# SCH__Atlas_2026-06-22.net
KiCad netlist of a schematic drawn in EasyEDA
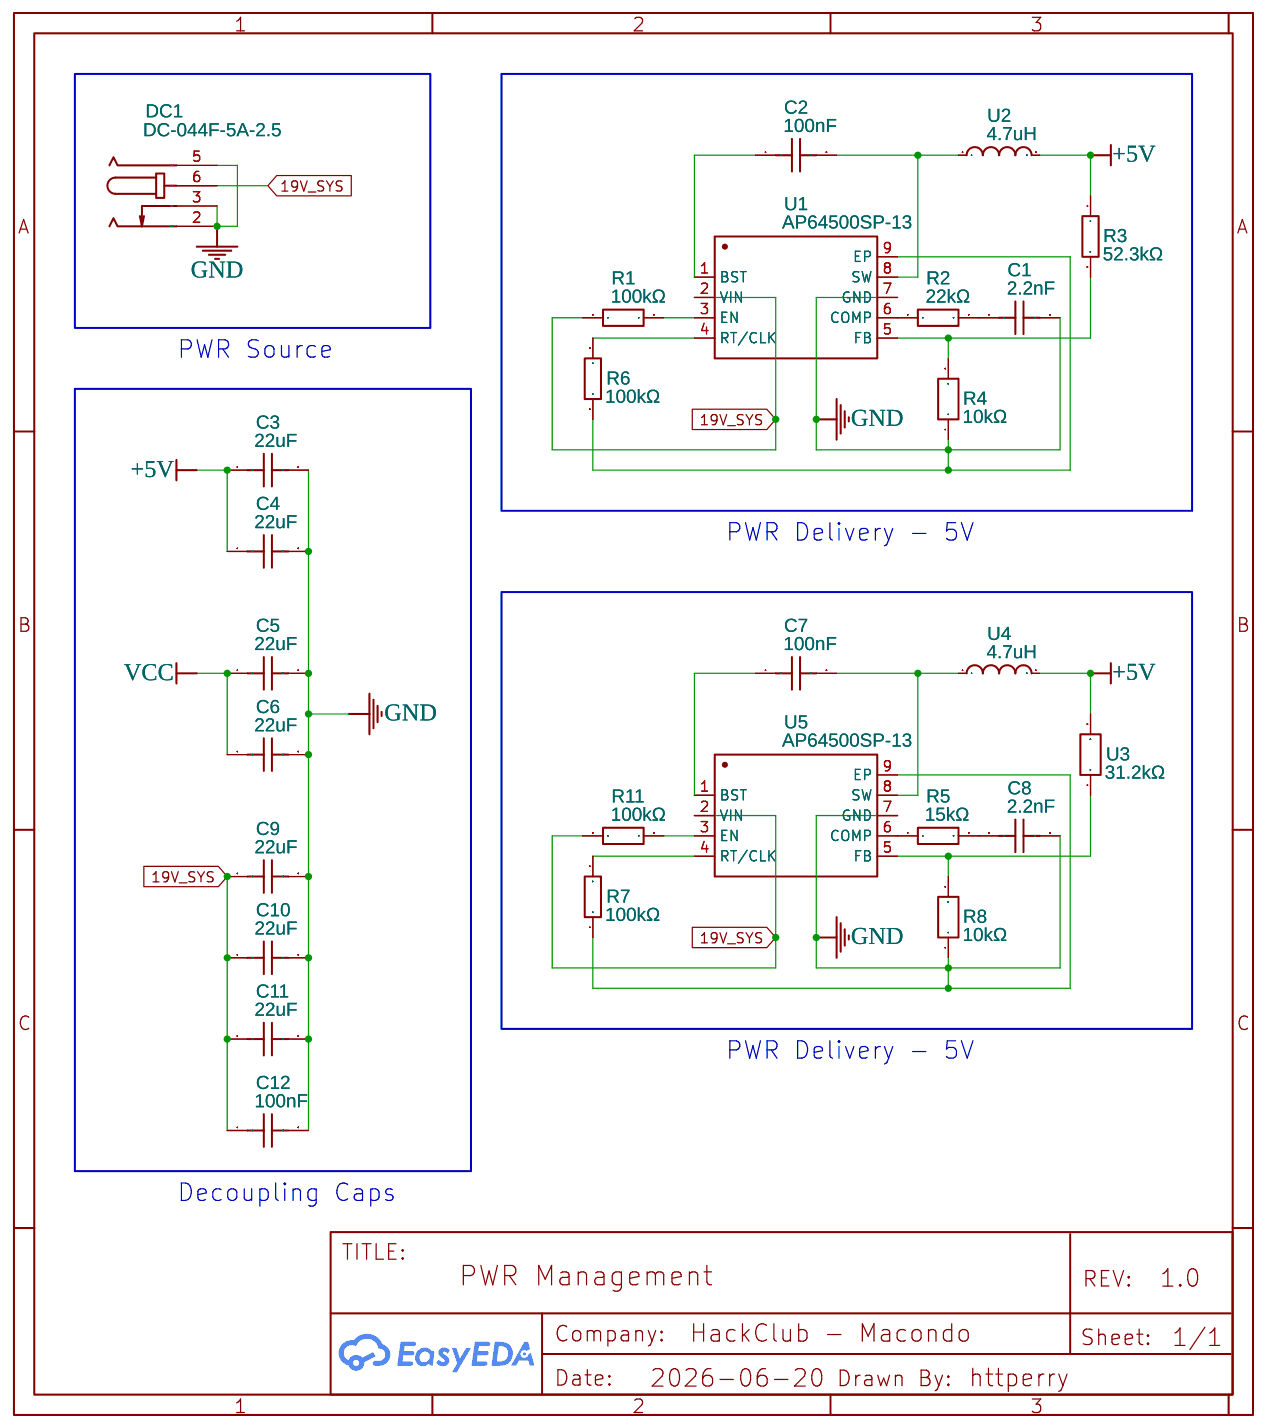
[diagram p0: PWR_Management]
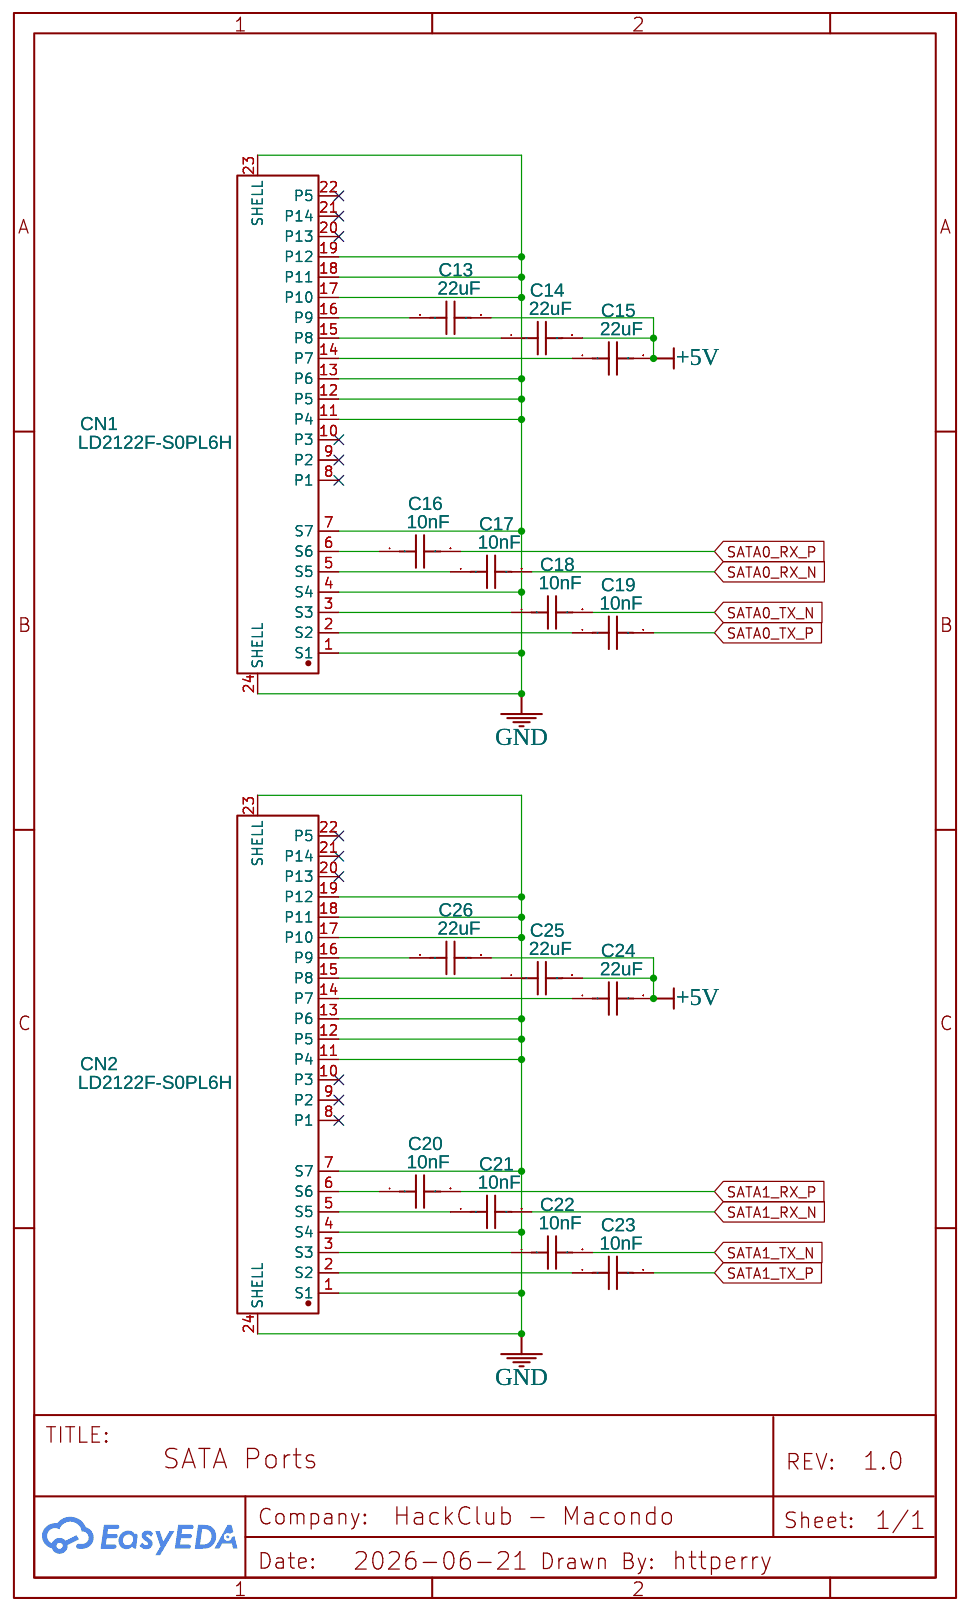
[diagram p1: SATA_Ports]
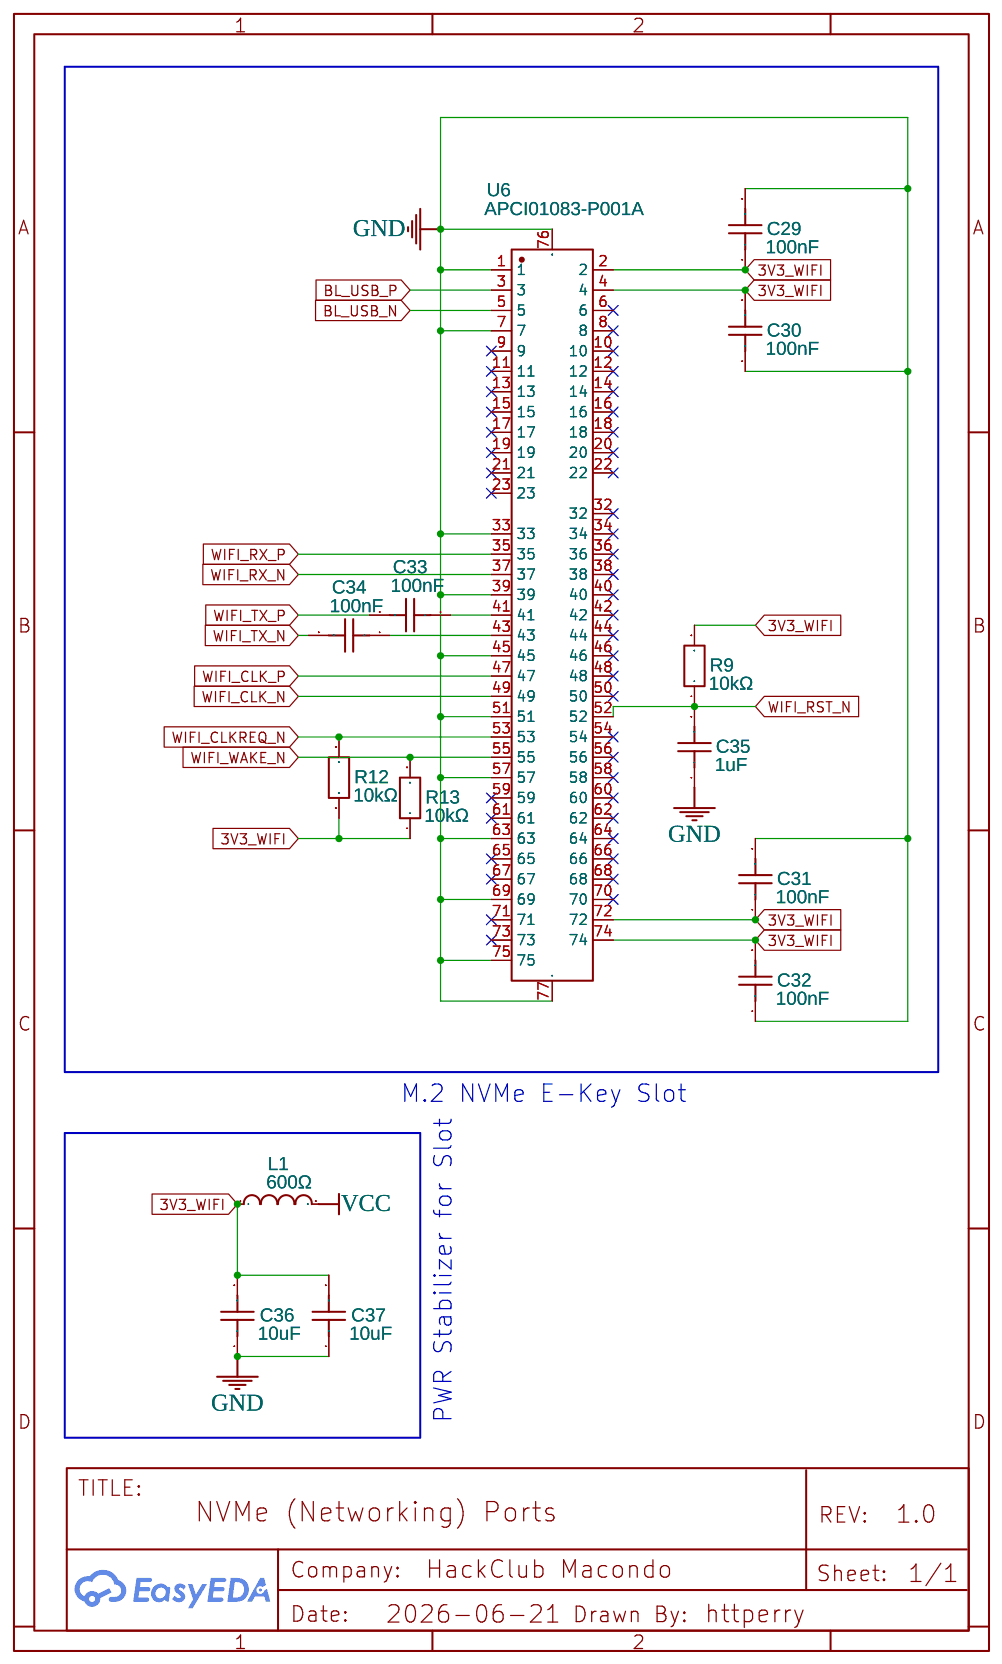
[diagram p2: NVMe_(Networking)_Ports]
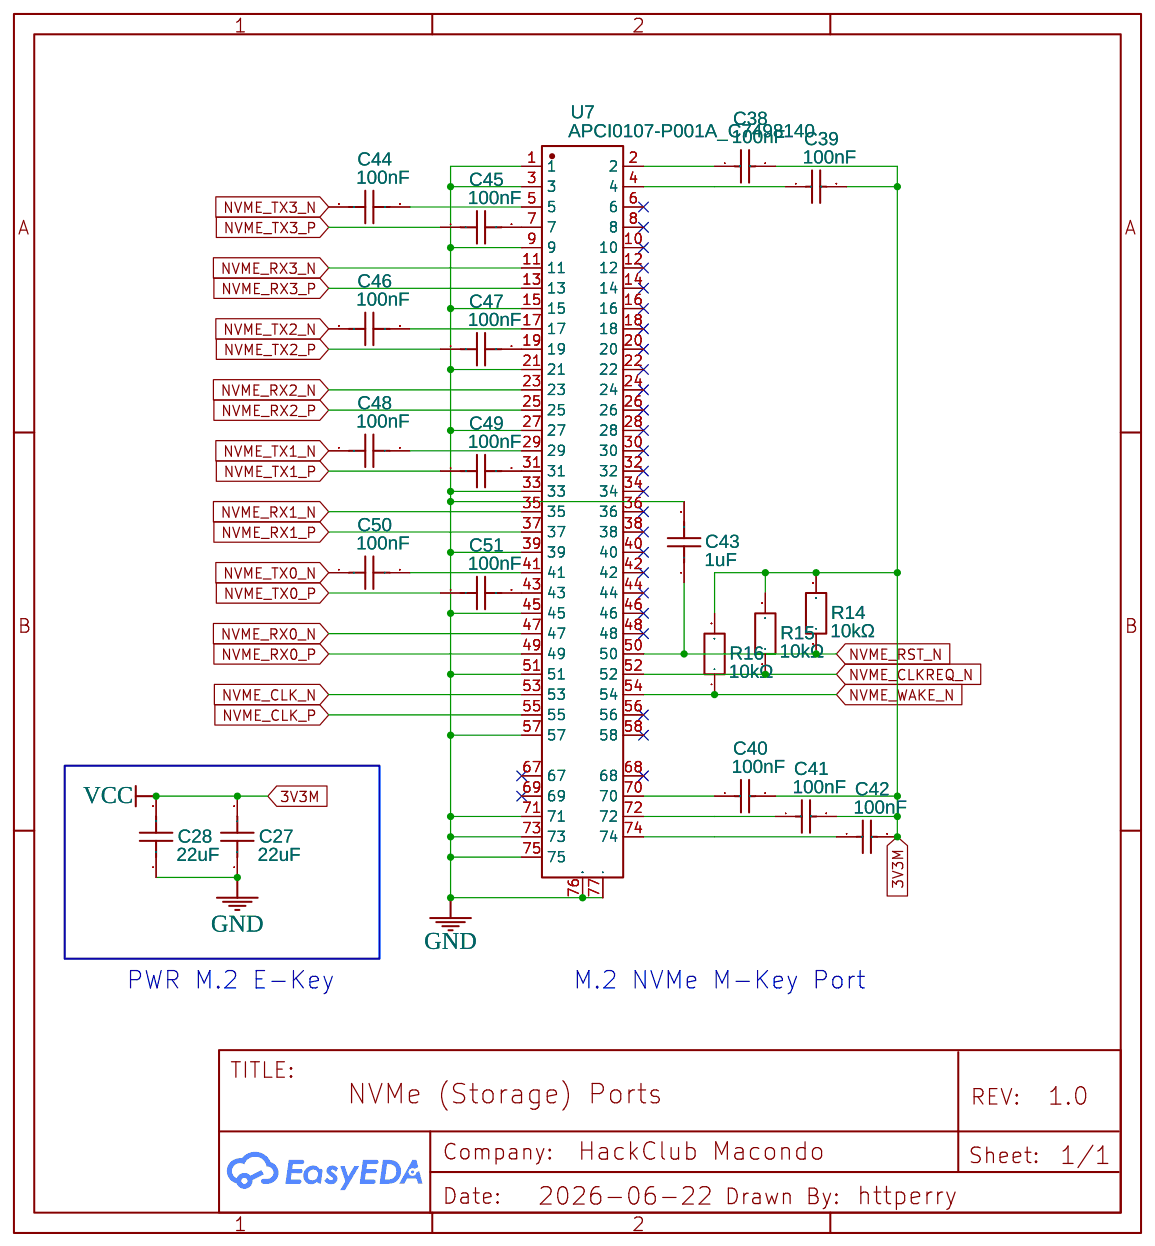
[diagram p3: NVMe_(Storage)_Ports]
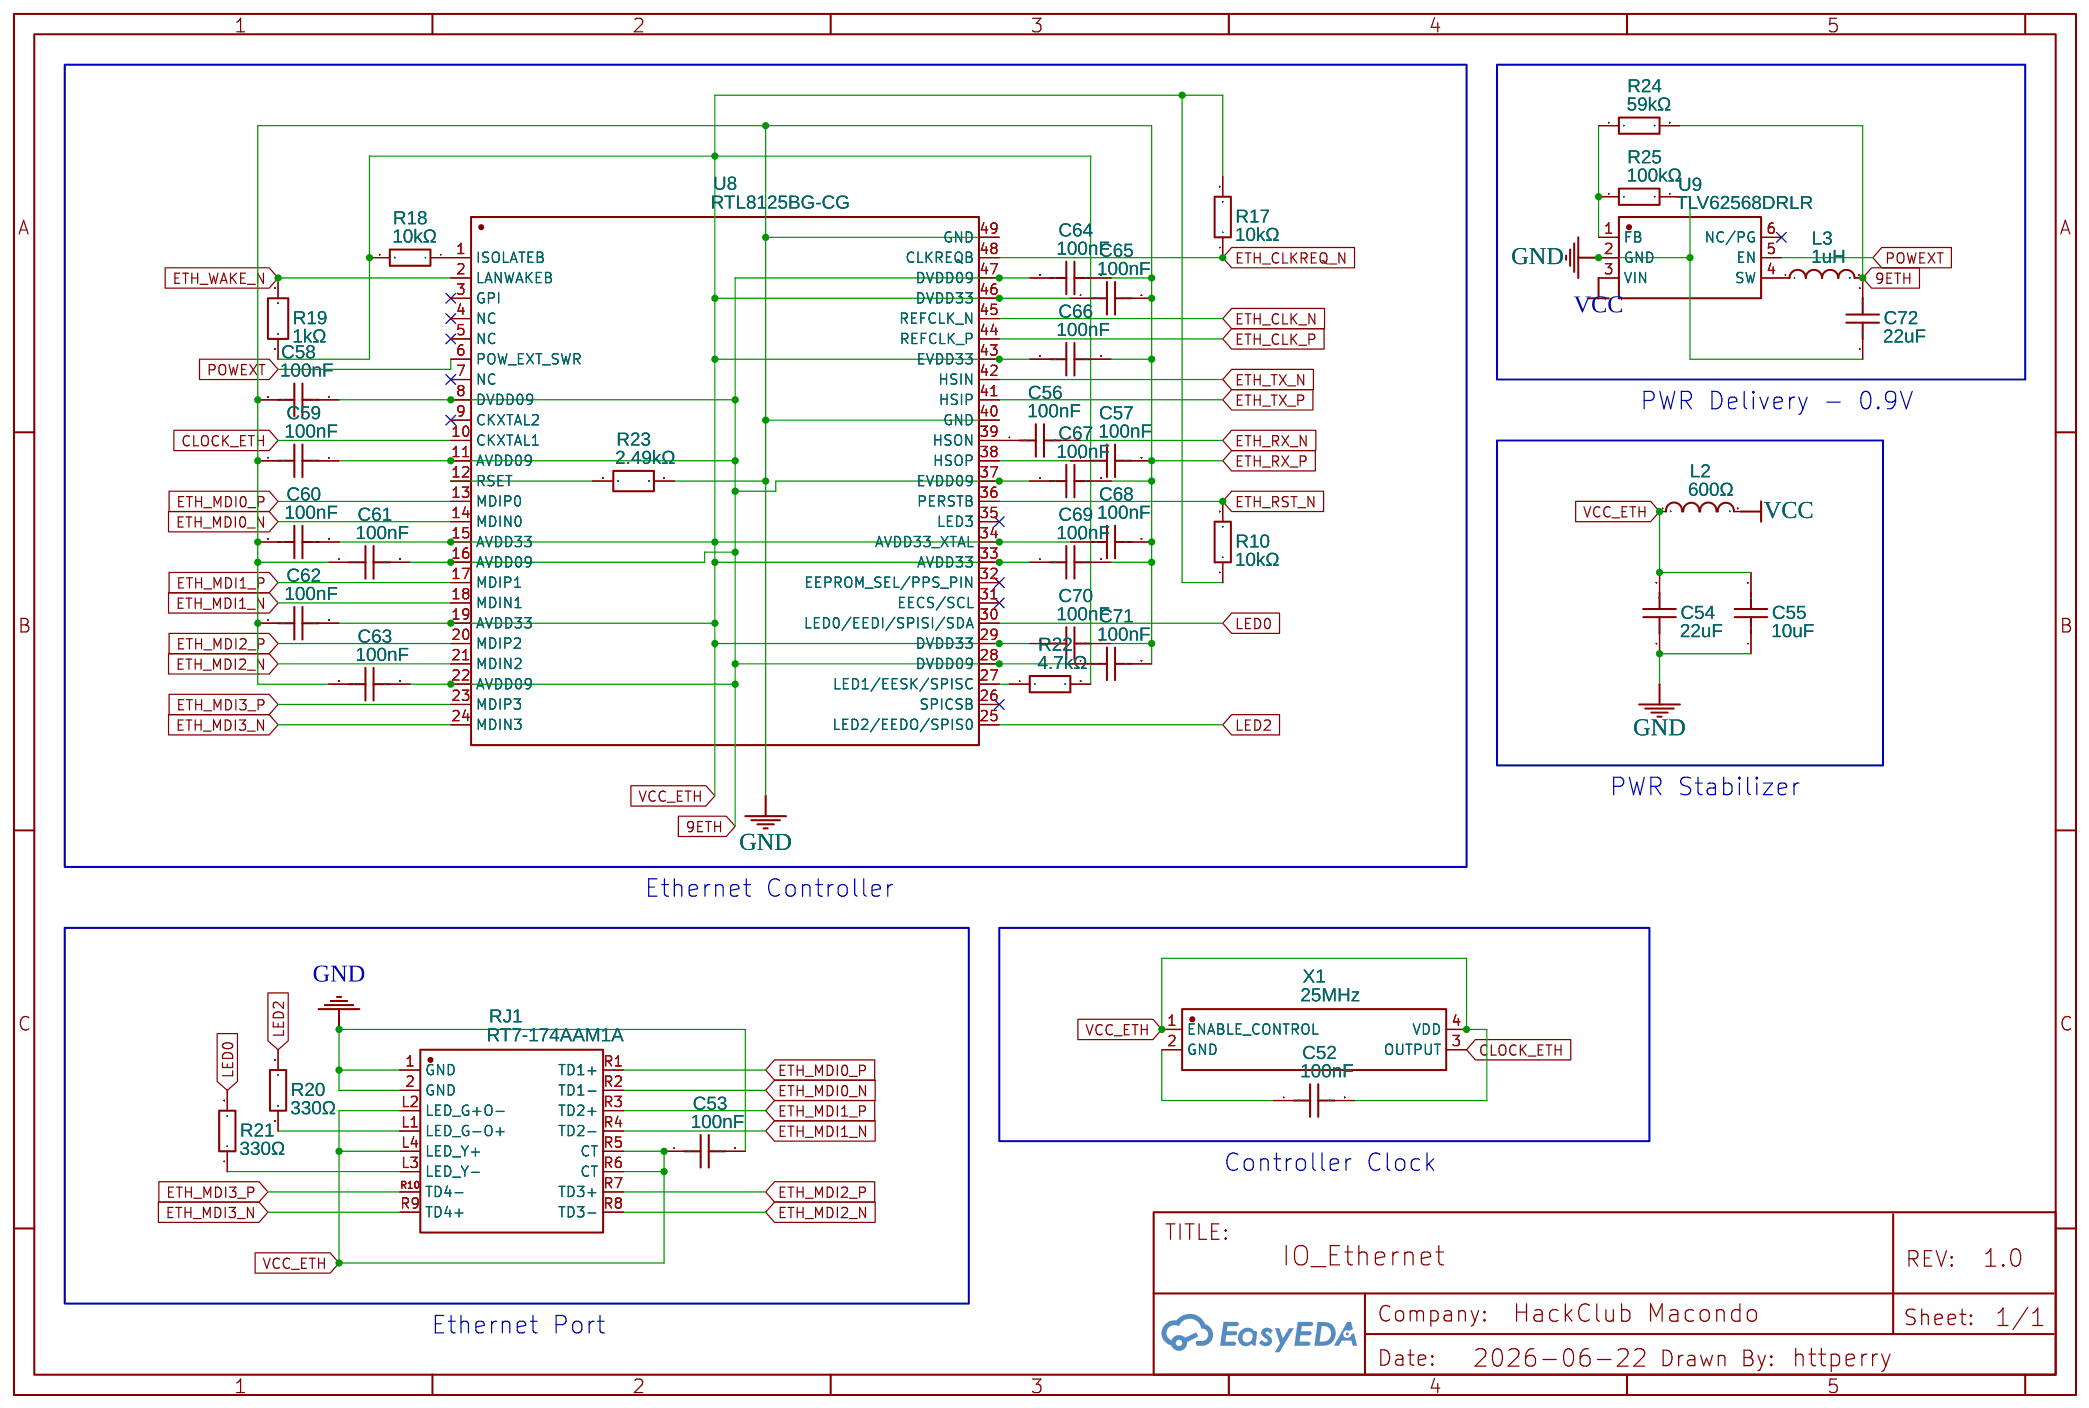
[diagram p4: IO_Ethernet]

(export (version "E")
  (design (tool "Eeschema 10.0.6"))
  (components
    (comp (ref "C1")
      (value "2.2nF")
      (fields
        (field (name "Manufacturer Part") "FCC0603B222K500CT")
        (field (name "Manufacturer") "FOJAN(富捷)")
      )
      (libsource (lib "") (part "FCC0603B222K500CT"))
    )
    (comp (ref "C2")
      (value "100nF")
      (fields
        (field (name "Manufacturer Part") "GRM188R71H104KA93D")
        (field (name "Manufacturer") "muRata(村田)")
      )
      (libsource (lib "") (part "GRM188R71H104KA93D"))
    )
    (comp (ref "C3")
      (value "22uF")
      (fields
        (field (name "Manufacturer Part") "HGC0603R5226M160NTHJ")
        (field (name "Manufacturer") "Chinocera(华瓷)")
      )
      (libsource (lib "") (part "HGC0603R5226M160NTHJ"))
    )
    (comp (ref "C4")
      (value "22uF")
      (fields
        (field (name "Manufacturer Part") "HGC0603R5226M160NTHJ")
        (field (name "Manufacturer") "Chinocera(华瓷)")
      )
      (libsource (lib "") (part "HGC0603R5226M160NTHJ"))
    )
    (comp (ref "C5")
      (value "22uF")
      (fields
        (field (name "Manufacturer Part") "HGC0603R5226M160NTHJ")
        (field (name "Manufacturer") "Chinocera(华瓷)")
      )
      (libsource (lib "") (part "HGC0603R5226M160NTHJ"))
    )
    (comp (ref "C6")
      (value "22uF")
      (fields
        (field (name "Manufacturer Part") "HGC0603R5226M160NTHJ")
        (field (name "Manufacturer") "Chinocera(华瓷)")
      )
      (libsource (lib "") (part "HGC0603R5226M160NTHJ"))
    )
    (comp (ref "C7")
      (value "100nF")
      (fields
        (field (name "Manufacturer Part") "GRM188R71H104KA93D")
        (field (name "Manufacturer") "muRata(村田)")
      )
      (libsource (lib "") (part "GRM188R71H104KA93D"))
    )
    (comp (ref "C8")
      (value "2.2nF")
      (fields
        (field (name "Manufacturer Part") "FCC0603B222K500CT")
        (field (name "Manufacturer") "FOJAN(富捷)")
      )
      (libsource (lib "") (part "FCC0603B222K500CT"))
    )
    (comp (ref "C9")
      (value "22uF")
      (fields
        (field (name "Manufacturer Part") "KCM55QR71H226KH13K")
        (field (name "Manufacturer") "muRata(村田)")
      )
      (libsource (lib "") (part "KCM55QR71H226KH13K"))
    )
    (comp (ref "C10")
      (value "22uF")
      (fields
        (field (name "Manufacturer Part") "KCM55QR71H226KH13K")
        (field (name "Manufacturer") "muRata(村田)")
      )
      (libsource (lib "") (part "KCM55QR71H226KH13K"))
    )
    (comp (ref "C11")
      (value "22uF")
      (fields
        (field (name "Manufacturer Part") "KCM55QR71H226KH13K")
        (field (name "Manufacturer") "muRata(村田)")
      )
      (libsource (lib "") (part "KCM55QR71H226KH13K"))
    )
    (comp (ref "C12")
      (value "100nF")
      (fields
        (field (name "Manufacturer Part") "GRM188R71H104KA93D")
        (field (name "Manufacturer") "muRata(村田)")
      )
      (libsource (lib "") (part "GRM188R71H104KA93D"))
    )
    (comp (ref "DC1")
      (value "DC-044F-5A-2.5")
      (fields (field (name "Manufacturer") "XKB Connection(中国星坤)"))
      (libsource (lib "") (part "DC-044F-5A-2.5"))
    )
    (comp (ref "R1")
      (value "100kΩ")
      (fields (field (name "Manufacturer Part") "RS-03K1003FT") (field (name "Manufacturer") "FH(风华)"))
      (libsource (lib "") (part "RS-03K1003FT_C115320_1"))
    )
    (comp (ref "R2")
      (value "22kΩ")
      (fields (field (name "Manufacturer Part") "RS-03K2202FT") (field (name "Manufacturer") "FH(风华)"))
      (libsource (lib "") (part "RS-03K2202FT"))
    )
    (comp (ref "R3")
      (value "52.3kΩ")
      (fields (field (name "Manufacturer Part") "RS-03K5232FT") (field (name "Manufacturer") "FH(风华)"))
      (libsource (lib "") (part "RS-03K5232FT"))
    )
    (comp (ref "R4")
      (value "10kΩ")
      (fields (field (name "Manufacturer Part") "AR03BTS1002") (field (name "Manufacturer") "Viking(光颉)"))
      (libsource (lib "") (part "AR03BTS1002"))
    )
    (comp (ref "R5")
      (value "15kΩ")
      (fields (field (name "Manufacturer Part") "CR0603FA1502G") (field (name "Manufacturer") "LIZ(丽智电子)"))
      (libsource (lib "") (part "CR0603FA1502G"))
    )
    (comp (ref "R6")
      (value "100kΩ")
      (fields (field (name "Manufacturer Part") "RS-03K1003FT") (field (name "Manufacturer") "FH(风华)"))
      (libsource (lib "") (part "RS-03K1003FT_C115320"))
    )
    (comp (ref "R7")
      (value "100kΩ")
      (fields (field (name "Manufacturer Part") "RS-03K1003FT") (field (name "Manufacturer") "FH(风华)"))
      (libsource (lib "") (part "RS-03K1003FT_C115320"))
    )
    (comp (ref "R8")
      (value "10kΩ")
      (fields (field (name "Manufacturer Part") "AR03BTS1002") (field (name "Manufacturer") "Viking(光颉)"))
      (libsource (lib "") (part "AR03BTS1002"))
    )
    (comp (ref "R11")
      (value "100kΩ")
      (fields (field (name "Manufacturer Part") "RS-03K1003FT") (field (name "Manufacturer") "FH(风华)"))
      (libsource (lib "") (part "RS-03K1003FT_C115320_1"))
    )
    (comp (ref "U1")
      (value "AP64500SP-13")
      (fields (field (name "Manufacturer") "DIODES(美台)"))
      (libsource (lib "") (part "AP64500SP-13"))
    )
    (comp (ref "U2")
      (value "4.7uH")
      (fields (field (name "Manufacturer Part") "APH0630T4R7M") (field (name "Manufacturer") "APV(爱普微)"))
      (libsource (lib "") (part "APH0630T4R7M"))
    )
    (comp (ref "U3")
      (value "31.2kΩ")
      (fields (field (name "Manufacturer Part") "RT0603DRE0731K2L") (field (name "Manufacturer") "YAGEO(国巨)"))
      (libsource (lib "") (part "RT0603DRE0731K2L"))
    )
    (comp (ref "U4")
      (value "4.7uH")
      (fields (field (name "Manufacturer Part") "APH0630T4R7M") (field (name "Manufacturer") "APV(爱普微)"))
      (libsource (lib "") (part "APH0630T4R7M"))
    )
    (comp (ref "U5")
      (value "AP64500SP-13")
      (fields (field (name "Manufacturer") "DIODES(美台)"))
      (libsource (lib "") (part "AP64500SP-13"))
    )
    (comp (ref "C13")
      (value "22uF")
      (fields
        (field (name "Manufacturer Part") "HGC0603R5226M160NTHJ")
        (field (name "Manufacturer") "Chinocera(华瓷)")
      )
      (libsource (lib "") (part "HGC0603R5226M160NTHJ"))
    )
    (comp (ref "C14")
      (value "22uF")
      (fields
        (field (name "Manufacturer Part") "HGC0603R5226M160NTHJ")
        (field (name "Manufacturer") "Chinocera(华瓷)")
      )
      (libsource (lib "") (part "HGC0603R5226M160NTHJ"))
    )
    (comp (ref "C15")
      (value "22uF")
      (fields
        (field (name "Manufacturer Part") "HGC0603R5226M160NTHJ")
        (field (name "Manufacturer") "Chinocera(华瓷)")
      )
      (libsource (lib "") (part "HGC0603R5226M160NTHJ"))
    )
    (comp (ref "C16")
      (value "10nF")
      (fields
        (field (name "Manufacturer Part") "FCC0402B103K500AT")
        (field (name "Manufacturer") "FOJAN(富捷)")
      )
      (libsource (lib "") (part "FCC0402B103K500AT"))
    )
    (comp (ref "C17")
      (value "10nF")
      (fields
        (field (name "Manufacturer Part") "FCC0402B103K500AT")
        (field (name "Manufacturer") "FOJAN(富捷)")
      )
      (libsource (lib "") (part "FCC0402B103K500AT"))
    )
    (comp (ref "C18")
      (value "10nF")
      (fields
        (field (name "Manufacturer Part") "FCC0402B103K500AT")
        (field (name "Manufacturer") "FOJAN(富捷)")
      )
      (libsource (lib "") (part "FCC0402B103K500AT"))
    )
    (comp (ref "C19")
      (value "10nF")
      (fields
        (field (name "Manufacturer Part") "FCC0402B103K500AT")
        (field (name "Manufacturer") "FOJAN(富捷)")
      )
      (libsource (lib "") (part "FCC0402B103K500AT"))
    )
    (comp (ref "C20")
      (value "10nF")
      (fields
        (field (name "Manufacturer Part") "FCC0402B103K500AT")
        (field (name "Manufacturer") "FOJAN(富捷)")
      )
      (libsource (lib "") (part "FCC0402B103K500AT"))
    )
    (comp (ref "C21")
      (value "10nF")
      (fields
        (field (name "Manufacturer Part") "FCC0402B103K500AT")
        (field (name "Manufacturer") "FOJAN(富捷)")
      )
      (libsource (lib "") (part "FCC0402B103K500AT"))
    )
    (comp (ref "C22")
      (value "10nF")
      (fields
        (field (name "Manufacturer Part") "FCC0402B103K500AT")
        (field (name "Manufacturer") "FOJAN(富捷)")
      )
      (libsource (lib "") (part "FCC0402B103K500AT"))
    )
    (comp (ref "C23")
      (value "10nF")
      (fields
        (field (name "Manufacturer Part") "FCC0402B103K500AT")
        (field (name "Manufacturer") "FOJAN(富捷)")
      )
      (libsource (lib "") (part "FCC0402B103K500AT"))
    )
    (comp (ref "C24")
      (value "22uF")
      (fields
        (field (name "Manufacturer Part") "HGC0603R5226M160NTHJ")
        (field (name "Manufacturer") "Chinocera(华瓷)")
      )
      (libsource (lib "") (part "HGC0603R5226M160NTHJ"))
    )
    (comp (ref "C25")
      (value "22uF")
      (fields
        (field (name "Manufacturer Part") "HGC0603R5226M160NTHJ")
        (field (name "Manufacturer") "Chinocera(华瓷)")
      )
      (libsource (lib "") (part "HGC0603R5226M160NTHJ"))
    )
    (comp (ref "C26")
      (value "22uF")
      (fields
        (field (name "Manufacturer Part") "HGC0603R5226M160NTHJ")
        (field (name "Manufacturer") "Chinocera(华瓷)")
      )
      (libsource (lib "") (part "HGC0603R5226M160NTHJ"))
    )
    (comp (ref "CN1")
      (value "LD2122F-S0PL6H")
      (fields (field (name "Manufacturer") "FOXCONN(富士康)"))
      (libsource (lib "") (part "LD2122F-S0PL6H"))
    )
    (comp (ref "CN2")
      (value "LD2122F-S0PL6H")
      (fields (field (name "Manufacturer") "FOXCONN(富士康)"))
      (libsource (lib "") (part "LD2122F-S0PL6H"))
    )
    (comp (ref "C29")
      (value "100nF")
      (fields
        (field (name "Manufacturer Part") "CC0402KRX5R6BB104")
        (field (name "Manufacturer") "YAGEO(国巨)")
      )
      (libsource (lib "") (part "CC0402KRX5R6BB104"))
    )
    (comp (ref "C30")
      (value "100nF")
      (fields
        (field (name "Manufacturer Part") "CC0402KRX5R6BB104")
        (field (name "Manufacturer") "YAGEO(国巨)")
      )
      (libsource (lib "") (part "CC0402KRX5R6BB104"))
    )
    (comp (ref "C31")
      (value "100nF")
      (fields
        (field (name "Manufacturer Part") "CC0402KRX5R6BB104")
        (field (name "Manufacturer") "YAGEO(国巨)")
      )
      (libsource (lib "") (part "CC0402KRX5R6BB104"))
    )
    (comp (ref "C32")
      (value "100nF")
      (fields
        (field (name "Manufacturer Part") "CC0402KRX5R6BB104")
        (field (name "Manufacturer") "YAGEO(国巨)")
      )
      (libsource (lib "") (part "CC0402KRX5R6BB104"))
    )
    (comp (ref "C33")
      (value "100nF")
      (fields
        (field (name "Manufacturer Part") "CC0402KRX5R6BB104")
        (field (name "Manufacturer") "YAGEO(国巨)")
      )
      (libsource (lib "") (part "CC0402KRX5R6BB104_1"))
    )
    (comp (ref "C34")
      (value "100nF")
      (fields
        (field (name "Manufacturer Part") "CC0402KRX5R6BB104")
        (field (name "Manufacturer") "YAGEO(国巨)")
      )
      (libsource (lib "") (part "CC0402KRX5R6BB104_1"))
    )
    (comp (ref "C35")
      (value "1uF")
      (fields
        (field (name "Manufacturer Part") "TCC0402X5R105K160AT")
        (field (name "Manufacturer") "CCTC(三环)")
      )
      (libsource (lib "") (part "TCC0402X5R105K160AT"))
    )
    (comp (ref "C36")
      (value "10uF")
      (fields
        (field (name "Manufacturer Part") "CGA0805X5R106K500MT")
        (field (name "Manufacturer") "HRE(芯声)")
      )
      (libsource (lib "") (part "CGA0805X5R106K500MT"))
    )
    (comp (ref "C37")
      (value "10uF")
      (fields
        (field (name "Manufacturer Part") "CGA0805X5R106K500MT")
        (field (name "Manufacturer") "HRE(芯声)")
      )
      (libsource (lib "") (part "CGA0805X5R106K500MT"))
    )
    (comp (ref "L1")
      (value "600Ω")
      (fields (field (name "Manufacturer Part") "MPZ2012S601AT000") (field (name "Manufacturer") "TDK"))
      (libsource (lib "") (part "MPZ2012S601AT000"))
    )
    (comp (ref "R9")
      (value "10kΩ")
      (fields (field (name "Manufacturer Part") "FRC0402F1002TS") (field (name "Manufacturer") "FOJAN(富捷)"))
      (libsource (lib "") (part "FRC0402F1002TS"))
    )
    (comp (ref "R12")
      (value "10kΩ")
      (fields (field (name "Manufacturer Part") "FRC0402F1002TS") (field (name "Manufacturer") "FOJAN(富捷)"))
      (libsource (lib "") (part "FRC0402F1002TS"))
    )
    (comp (ref "R13")
      (value "10kΩ")
      (fields (field (name "Manufacturer Part") "FRC0402F1002TS") (field (name "Manufacturer") "FOJAN(富捷)"))
      (libsource (lib "") (part "FRC0402F1002TS"))
    )
    (comp (ref "U6")
      (value "APCI01083-P001A")
      (fields (field (name "Manufacturer") "LX(连欣科技)"))
      (libsource (lib "") (part "APCI01083-P001A"))
    )
    (comp (ref "C27")
      (value "22uF")
      (fields
        (field (name "Manufacturer Part") "CL21A226MAYNNNE")
        (field (name "Manufacturer") "SAMSUNG(三星)")
      )
      (libsource (lib "") (part "CL21A226MAYNNNE"))
    )
    (comp (ref "C28")
      (value "22uF")
      (fields
        (field (name "Manufacturer Part") "CL21A226MAYNNNE")
        (field (name "Manufacturer") "SAMSUNG(三星)")
      )
      (libsource (lib "") (part "CL21A226MAYNNNE"))
    )
    (comp (ref "C38")
      (value "100nF")
      (fields
        (field (name "Manufacturer Part") "CC0402KRX5R8BB104")
        (field (name "Manufacturer") "YAGEO(国巨)")
      )
      (libsource (lib "") (part "CC0402KRX5R8BB104"))
    )
    (comp (ref "C39")
      (value "100nF")
      (fields
        (field (name "Manufacturer Part") "CC0402KRX5R8BB104")
        (field (name "Manufacturer") "YAGEO(国巨)")
      )
      (libsource (lib "") (part "CC0402KRX5R8BB104"))
    )
    (comp (ref "C40")
      (value "100nF")
      (fields
        (field (name "Manufacturer Part") "CC0402KRX5R8BB104")
        (field (name "Manufacturer") "YAGEO(国巨)")
      )
      (libsource (lib "") (part "CC0402KRX5R8BB104"))
    )
    (comp (ref "C41")
      (value "100nF")
      (fields
        (field (name "Manufacturer Part") "CC0402KRX5R8BB104")
        (field (name "Manufacturer") "YAGEO(国巨)")
      )
      (libsource (lib "") (part "CC0402KRX5R8BB104"))
    )
    (comp (ref "C42")
      (value "100nF")
      (fields
        (field (name "Manufacturer Part") "CC0402KRX5R8BB104")
        (field (name "Manufacturer") "YAGEO(国巨)")
      )
      (libsource (lib "") (part "CC0402KRX5R8BB104"))
    )
    (comp (ref "C43")
      (value "1uF")
      (fields
        (field (name "Manufacturer Part") "HGC0402R5105K500NTEJ")
        (field (name "Manufacturer") "Chinocera(华瓷)")
      )
      (libsource (lib "") (part "HGC0402R5105K500NTEJ"))
    )
    (comp (ref "C44")
      (value "100nF")
      (fields
        (field (name "Manufacturer Part") "GRM155R71H104KE14J")
        (field (name "Manufacturer") "muRata(村田)")
      )
      (libsource (lib "") (part "GRM155R71H104KE14J"))
    )
    (comp (ref "C45")
      (value "100nF")
      (fields
        (field (name "Manufacturer Part") "GRM155R71H104KE14J")
        (field (name "Manufacturer") "muRata(村田)")
      )
      (libsource (lib "") (part "GRM155R71H104KE14J"))
    )
    (comp (ref "C46")
      (value "100nF")
      (fields
        (field (name "Manufacturer Part") "GRM155R71H104KE14J")
        (field (name "Manufacturer") "muRata(村田)")
      )
      (libsource (lib "") (part "GRM155R71H104KE14J"))
    )
    (comp (ref "C47")
      (value "100nF")
      (fields
        (field (name "Manufacturer Part") "GRM155R71H104KE14J")
        (field (name "Manufacturer") "muRata(村田)")
      )
      (libsource (lib "") (part "GRM155R71H104KE14J"))
    )
    (comp (ref "C48")
      (value "100nF")
      (fields
        (field (name "Manufacturer Part") "GRM155R71H104KE14J")
        (field (name "Manufacturer") "muRata(村田)")
      )
      (libsource (lib "") (part "GRM155R71H104KE14J"))
    )
    (comp (ref "C49")
      (value "100nF")
      (fields
        (field (name "Manufacturer Part") "GRM155R71H104KE14J")
        (field (name "Manufacturer") "muRata(村田)")
      )
      (libsource (lib "") (part "GRM155R71H104KE14J"))
    )
    (comp (ref "C50")
      (value "100nF")
      (fields
        (field (name "Manufacturer Part") "GRM155R71H104KE14J")
        (field (name "Manufacturer") "muRata(村田)")
      )
      (libsource (lib "") (part "GRM155R71H104KE14J"))
    )
    (comp (ref "C51")
      (value "100nF")
      (fields
        (field (name "Manufacturer Part") "GRM155R71H104KE14J")
        (field (name "Manufacturer") "muRata(村田)")
      )
      (libsource (lib "") (part "GRM155R71H104KE14J"))
    )
    (comp (ref "R14")
      (value "10kΩ")
      (fields (field (name "Manufacturer Part") "FRC0402F1002TS") (field (name "Manufacturer") "FOJAN(富捷)"))
      (libsource (lib "") (part "FRC0402F1002TS"))
    )
    (comp (ref "R15")
      (value "10kΩ")
      (fields (field (name "Manufacturer Part") "FRC0402F1002TS") (field (name "Manufacturer") "FOJAN(富捷)"))
      (libsource (lib "") (part "FRC0402F1002TS"))
    )
    (comp (ref "R16")
      (value "10kΩ")
      (fields (field (name "Manufacturer Part") "FRC0402F1002TS") (field (name "Manufacturer") "FOJAN(富捷)"))
      (libsource (lib "") (part "FRC0402F1002TS"))
    )
    (comp (ref "U7")
      (value "APCI0107-P001A_C7498140")
      (fields (field (name "Manufacturer Part") "APCI0107-P001A") (field (name "Manufacturer") "LX(连欣科技)"))
      (libsource (lib "") (part "APCI0107-P001A_C7498140"))
    )
    (comp (ref "C52")
      (value "100nF")
      (fields
        (field (name "Manufacturer Part") "GRM155R71H104KE14J")
        (field (name "Manufacturer") "muRata(村田)")
      )
      (libsource (lib "") (part "GRM155R71H104KE14J"))
    )
    (comp (ref "C53")
      (value "100nF")
      (fields
        (field (name "Manufacturer Part") "GRM155R71H104KE14J")
        (field (name "Manufacturer") "muRata(村田)")
      )
      (libsource (lib "") (part "GRM155R71H104KE14J"))
    )
    (comp (ref "C54")
      (value "22uF")
      (fields
        (field (name "Manufacturer Part") "GRT21BR61E226ME13L")
        (field (name "Manufacturer") "muRata(村田)")
      )
      (libsource (lib "") (part "GRT21BR61E226ME13L"))
    )
    (comp (ref "C55")
      (value "10uF")
      (fields
        (field (name "Manufacturer Part") "TCC0805X5R106K250FT")
        (field (name "Manufacturer") "CCTC(三环)")
      )
      (libsource (lib "") (part "TCC0805X5R106K250FT"))
    )
    (comp (ref "C56")
      (value "100nF")
      (fields
        (field (name "Manufacturer Part") "GRM155R71H104KE14J")
        (field (name "Manufacturer") "muRata(村田)")
      )
      (libsource (lib "") (part "GRM155R71H104KE14J"))
    )
    (comp (ref "C57")
      (value "100nF")
      (fields
        (field (name "Manufacturer Part") "GRM155R71H104KE14J")
        (field (name "Manufacturer") "muRata(村田)")
      )
      (libsource (lib "") (part "GRM155R71H104KE14J"))
    )
    (comp (ref "C58")
      (value "100nF")
      (fields
        (field (name "Manufacturer Part") "GRM155R71H104KE14J")
        (field (name "Manufacturer") "muRata(村田)")
      )
      (libsource (lib "") (part "GRM155R71H104KE14J_1"))
    )
    (comp (ref "C59")
      (value "100nF")
      (fields
        (field (name "Manufacturer Part") "GRM155R71H104KE14J")
        (field (name "Manufacturer") "muRata(村田)")
      )
      (libsource (lib "") (part "GRM155R71H104KE14J"))
    )
    (comp (ref "C60")
      (value "100nF")
      (fields
        (field (name "Manufacturer Part") "GRM155R71H104KE14J")
        (field (name "Manufacturer") "muRata(村田)")
      )
      (libsource (lib "") (part "GRM155R71H104KE14J"))
    )
    (comp (ref "C61")
      (value "100nF")
      (fields
        (field (name "Manufacturer Part") "GRM155R71H104KE14J")
        (field (name "Manufacturer") "muRata(村田)")
      )
      (libsource (lib "") (part "GRM155R71H104KE14J"))
    )
    (comp (ref "C62")
      (value "100nF")
      (fields
        (field (name "Manufacturer Part") "GRM155R71H104KE14J")
        (field (name "Manufacturer") "muRata(村田)")
      )
      (libsource (lib "") (part "GRM155R71H104KE14J"))
    )
    (comp (ref "C63")
      (value "100nF")
      (fields
        (field (name "Manufacturer Part") "GRM155R71H104KE14J")
        (field (name "Manufacturer") "muRata(村田)")
      )
      (libsource (lib "") (part "GRM155R71H104KE14J"))
    )
    (comp (ref "C64")
      (value "100nF")
      (fields
        (field (name "Manufacturer Part") "GRM155R71H104KE14J")
        (field (name "Manufacturer") "muRata(村田)")
      )
      (libsource (lib "") (part "GRM155R71H104KE14J"))
    )
    (comp (ref "C65")
      (value "100nF")
      (fields
        (field (name "Manufacturer Part") "GRM155R71H104KE14J")
        (field (name "Manufacturer") "muRata(村田)")
      )
      (libsource (lib "") (part "GRM155R71H104KE14J"))
    )
    (comp (ref "C66")
      (value "100nF")
      (fields
        (field (name "Manufacturer Part") "GRM155R71H104KE14J")
        (field (name "Manufacturer") "muRata(村田)")
      )
      (libsource (lib "") (part "GRM155R71H104KE14J"))
    )
    (comp (ref "C67")
      (value "100nF")
      (fields
        (field (name "Manufacturer Part") "GRM155R71H104KE14J")
        (field (name "Manufacturer") "muRata(村田)")
      )
      (libsource (lib "") (part "GRM155R71H104KE14J"))
    )
    (comp (ref "C68")
      (value "100nF")
      (fields
        (field (name "Manufacturer Part") "GRM155R71H104KE14J")
        (field (name "Manufacturer") "muRata(村田)")
      )
      (libsource (lib "") (part "GRM155R71H104KE14J"))
    )
    (comp (ref "C69")
      (value "100nF")
      (fields
        (field (name "Manufacturer Part") "GRM155R71H104KE14J")
        (field (name "Manufacturer") "muRata(村田)")
      )
      (libsource (lib "") (part "GRM155R71H104KE14J"))
    )
    (comp (ref "C70")
      (value "100nF")
      (fields
        (field (name "Manufacturer Part") "GRM155R71H104KE14J")
        (field (name "Manufacturer") "muRata(村田)")
      )
      (libsource (lib "") (part "GRM155R71H104KE14J"))
    )
    (comp (ref "C71")
      (value "100nF")
      (fields
        (field (name "Manufacturer Part") "GRM155R71H104KE14J")
        (field (name "Manufacturer") "muRata(村田)")
      )
      (libsource (lib "") (part "GRM155R71H104KE14J"))
    )
    (comp (ref "C72")
      (value "22uF")
      (fields
        (field (name "Manufacturer Part") "GRT21BR61E226ME13L")
        (field (name "Manufacturer") "muRata(村田)")
      )
      (libsource (lib "") (part "GRT21BR61E226ME13L"))
    )
    (comp (ref "L2")
      (value "600Ω")
      (fields (field (name "Manufacturer Part") "MPZ2012S601AT000") (field (name "Manufacturer") "TDK"))
      (libsource (lib "") (part "MPZ2012S601AT000"))
    )
    (comp (ref "L3")
      (value "1uH")
      (fields (field (name "Manufacturer Part") "XRIM201612S1R0MBCA") (field (name "Manufacturer") "XR(祥如)"))
      (libsource (lib "") (part "XRIM201612S1R0MBCA"))
    )
    (comp (ref "R10")
      (value "10kΩ")
      (fields (field (name "Manufacturer Part") "ERA2AEB103X") (field (name "Manufacturer") "PANASONIC(松下)"))
      (libsource (lib "") (part "ERA2AEB103X"))
    )
    (comp (ref "R17")
      (value "10kΩ")
      (fields (field (name "Manufacturer Part") "ERA2AEB103X") (field (name "Manufacturer") "PANASONIC(松下)"))
      (libsource (lib "") (part "ERA2AEB103X"))
    )
    (comp (ref "R18")
      (value "10kΩ")
      (fields (field (name "Manufacturer Part") "ERA2AEB103X") (field (name "Manufacturer") "PANASONIC(松下)"))
      (libsource (lib "") (part "ERA2AEB103X_1"))
    )
    (comp (ref "R19")
      (value "1kΩ")
      (fields (field (name "Manufacturer Part") "RT0402BRD071KL") (field (name "Manufacturer") "YAGEO(国巨)"))
      (libsource (lib "") (part "RT0402BRD071KL"))
    )
    (comp (ref "R20")
      (value "330Ω")
      (fields (field (name "Manufacturer Part") "RC0402JR-07330RL") (field (name "Manufacturer") "YAGEO(国巨)"))
      (libsource (lib "") (part "RC0402JR-07330RL_1"))
    )
    (comp (ref "R21")
      (value "330Ω")
      (fields (field (name "Manufacturer Part") "RC0402JR-07330RL") (field (name "Manufacturer") "YAGEO(国巨)"))
      (libsource (lib "") (part "RC0402JR-07330RL"))
    )
    (comp (ref "R22")
      (value "4.7kΩ")
      (fields (field (name "Manufacturer Part") "RC0402FR-074K7L") (field (name "Manufacturer") "YAGEO(国巨)"))
      (libsource (lib "") (part "RC0402FR-074K7L"))
    )
    (comp (ref "R23")
      (value "2.49kΩ")
      (fields (field (name "Manufacturer Part") "FRC0402F2491TS") (field (name "Manufacturer") "FOJAN(富捷)"))
      (libsource (lib "") (part "FRC0402F2491TS"))
    )
    (comp (ref "R24")
      (value "59kΩ")
      (fields (field (name "Manufacturer Part") "RS-03K5902FT") (field (name "Manufacturer") "FH(风华)"))
      (libsource (lib "") (part "RS-03K5902FT"))
    )
    (comp (ref "R25")
      (value "100kΩ")
      (fields (field (name "Manufacturer Part") "RS-03K1003FT") (field (name "Manufacturer") "FH(风华)"))
      (libsource (lib "") (part "RS-03K1003FT_C115320"))
    )
    (comp (ref "RJ1")
      (value "RT7-174AAM1A")
      (fields (field (name "Manufacturer") "UDE(涌德电子)"))
      (libsource (lib "") (part "RT7-174AAM1A"))
    )
    (comp (ref "U8")
      (value "RTL8125BG-CG")
      (fields (field (name "Manufacturer") "REALTEK(瑞昱)"))
      (libsource (lib "") (part "RTL8125BG-CG"))
    )
    (comp (ref "U9")
      (value "TLV62568DRLR")
      (fields (field (name "Manufacturer") "TI(德州仪器)"))
      (libsource (lib "") (part "TLV62568DRLR"))
    )
    (comp (ref "X1")
      (value "25MHz")
      (fields
        (field (name "Manufacturer Part") "SX3M25.000B10G40TNN")
        (field (name "Manufacturer") "SCTF(星通时频)")
      )
      (libsource (lib "") (part "SX3M25.000B10G40TNN"))
    )
  )
  (nets
    (net (code "1") (name "+5V") (class "Default")
      (node (ref "C13") (pin "2") (pinfunction "2_2") (pintype "unspecified"))
      (node (ref "C14") (pin "2") (pinfunction "2_2") (pintype "unspecified"))
      (node (ref "C15") (pin "2") (pinfunction "2_2") (pintype "unspecified"))
      (node (ref "C24") (pin "2") (pinfunction "2_2") (pintype "unspecified"))
      (node (ref "C25") (pin "2") (pinfunction "2_2") (pintype "unspecified"))
      (node (ref "C26") (pin "2") (pinfunction "2_2") (pintype "unspecified"))
      (node (ref "C3") (pin "1") (pinfunction "1_1") (pintype "unspecified"))
      (node (ref "C4") (pin "1") (pinfunction "1_1") (pintype "unspecified"))
      (node (ref "R3") (pin "1") (pinfunction "1_1") (pintype "unspecified"))
      (node (ref "U2") (pin "2") (pinfunction "2_2") (pintype "unspecified"))
      (node (ref "U3") (pin "2") (pinfunction "2_2") (pintype "unspecified"))
      (node (ref "U4") (pin "2") (pinfunction "2_2") (pintype "unspecified"))
    )
    (net (code "2") (name "3V3M") (class "Default")
      (node (ref "C27") (pin "2") (pinfunction "2_2") (pintype "unspecified"))
      (node (ref "C28") (pin "2") (pinfunction "2_2") (pintype "unspecified"))
      (node (ref "C38") (pin "2") (pinfunction "2_2") (pintype "input"))
      (node (ref "C39") (pin "2") (pinfunction "2_2") (pintype "input"))
      (node (ref "C40") (pin "2") (pinfunction "2_2") (pintype "input"))
      (node (ref "C41") (pin "2") (pinfunction "2_2") (pintype "input"))
      (node (ref "C42") (pin "2") (pinfunction "2_2") (pintype "input"))
      (node (ref "C5") (pin "1") (pinfunction "1_1") (pintype "unspecified"))
      (node (ref "C6") (pin "1") (pinfunction "1_1") (pintype "unspecified"))
      (node (ref "L1") (pin "2") (pinfunction "2_2") (pintype "unspecified"))
      (node (ref "L2") (pin "2") (pinfunction "2_2") (pintype "unspecified"))
      (node (ref "R14") (pin "2") (pinfunction "2_2") (pintype "unspecified"))
      (node (ref "R15") (pin "2") (pinfunction "2_2") (pintype "unspecified"))
      (node (ref "R16") (pin "2") (pinfunction "2_2") (pintype "unspecified"))
      (node (ref "U9") (pin "3") (pinfunction "VIN_3") (pintype "unspecified"))
    )
    (net (code "3") (name "3V3_WIFI") (class "Default")
      (node (ref "C29") (pin "1") (pinfunction "1_1") (pintype "unspecified"))
      (node (ref "C30") (pin "2") (pinfunction "2_2") (pintype "unspecified"))
      (node (ref "C31") (pin "1") (pinfunction "1_1") (pintype "unspecified"))
      (node (ref "C32") (pin "2") (pinfunction "2_2") (pintype "unspecified"))
      (node (ref "C36") (pin "2") (pinfunction "2_2") (pintype "unspecified"))
      (node (ref "C37") (pin "2") (pinfunction "2_2") (pintype "unspecified"))
      (node (ref "L1") (pin "1") (pinfunction "1_1") (pintype "unspecified"))
      (node (ref "R12") (pin "1") (pinfunction "1_1") (pintype "unspecified"))
      (node (ref "R13") (pin "1") (pinfunction "1_1") (pintype "unspecified"))
      (node (ref "R9") (pin "2") (pinfunction "2_2") (pintype "unspecified"))
      (node (ref "U6") (pin "2") (pinfunction "2_2") (pintype "unspecified"))
      (node (ref "U6") (pin "4") (pinfunction "4_4") (pintype "unspecified"))
      (node (ref "U6") (pin "72") (pinfunction "72_72") (pintype "unspecified"))
      (node (ref "U6") (pin "74") (pinfunction "74_74") (pintype "unspecified"))
    )
    (net (code "4") (name "9ETH") (class "Default")
      (node (ref "C58") (pin "1") (pinfunction "1_1") (pintype "unspecified"))
      (node (ref "C59") (pin "2") (pinfunction "2_2") (pintype "unspecified"))
      (node (ref "C61") (pin "2") (pinfunction "2_2") (pintype "unspecified"))
      (node (ref "C63") (pin "2") (pinfunction "2_2") (pintype "unspecified"))
      (node (ref "C64") (pin "1") (pinfunction "1_1") (pintype "unspecified"))
      (node (ref "C67") (pin "1") (pinfunction "1_1") (pintype "unspecified"))
      (node (ref "C71") (pin "1") (pinfunction "1_1") (pintype "unspecified"))
      (node (ref "C72") (pin "2") (pinfunction "2_2") (pintype "unspecified"))
      (node (ref "L3") (pin "2") (pinfunction "2_2") (pintype "unspecified"))
      (node (ref "R24") (pin "2") (pinfunction "2_2") (pintype "unspecified"))
      (node (ref "U8") (pin "11") (pinfunction "AVDD09_11") (pintype "unspecified"))
      (node (ref "U8") (pin "16") (pinfunction "AVDD09_16") (pintype "unspecified"))
      (node (ref "U8") (pin "22") (pinfunction "AVDD09_22") (pintype "unspecified"))
      (node (ref "U8") (pin "28") (pinfunction "DVDD09_28") (pintype "unspecified"))
      (node (ref "U8") (pin "37") (pinfunction "EVDD09_37") (pintype "unspecified"))
      (node (ref "U8") (pin "47") (pinfunction "DVDD09_47") (pintype "unspecified"))
      (node (ref "U8") (pin "8") (pinfunction "DVDD09_8") (pintype "unspecified"))
    )
    (net (code "5") (name "19V_SYS") (class "Default")
      (node (ref "C10") (pin "1") (pinfunction "1_1") (pintype "unspecified"))
      (node (ref "C11") (pin "1") (pinfunction "1_1") (pintype "unspecified"))
      (node (ref "C12") (pin "1") (pinfunction "1_1") (pintype "unspecified"))
      (node (ref "C9") (pin "1") (pinfunction "1_1") (pintype "unspecified"))
      (node (ref "DC1") (pin "6") (pinfunction "6_6") (pintype "unspecified"))
      (node (ref "R1") (pin "1") (pinfunction "1_1") (pintype "unspecified"))
      (node (ref "R11") (pin "1") (pinfunction "1_1") (pintype "unspecified"))
      (node (ref "U1") (pin "2") (pinfunction "VIN_2") (pintype "unspecified"))
      (node (ref "U5") (pin "2") (pinfunction "VIN_2") (pintype "unspecified"))
    )
    (net (code "6") (name "BL_USB_N") (class "Default")
      (node (ref "U6") (pin "5") (pinfunction "5_5") (pintype "unspecified"))
    )
    (net (code "7") (name "BL_USB_P") (class "Default")
      (node (ref "U6") (pin "3") (pinfunction "3_3") (pintype "unspecified"))
    )
    (net (code "8") (name "CLOCK_ETH") (class "Default")
      (node (ref "U8") (pin "10") (pinfunction "CKXTAL1_10") (pintype "unspecified"))
      (node (ref "X1") (pin "3") (pinfunction "OUTPUT_3") (pintype "unspecified"))
    )
    (net (code "9") (name "ETH_CLKREQ_N") (class "Default")
      (node (ref "R17") (pin "1") (pinfunction "1_1") (pintype "input"))
      (node (ref "U8") (pin "48") (pinfunction "CLKREQB_48") (pintype "unspecified"))
    )
    (net (code "10") (name "ETH_CLK_N") (class "Default")
      (node (ref "U8") (pin "45") (pinfunction "REFCLK_N_45") (pintype "unspecified"))
    )
    (net (code "11") (name "ETH_CLK_P") (class "Default")
      (node (ref "U8") (pin "44") (pinfunction "REFCLK_P_44") (pintype "unspecified"))
    )
    (net (code "12") (name "ETH_MDI0_N") (class "Default")
      (node (ref "RJ1") (pin "R2") (pinfunction "TD1-_R2") (pintype "unspecified"))
      (node (ref "U8") (pin "14") (pinfunction "MDIN0_14") (pintype "unspecified"))
    )
    (net (code "13") (name "ETH_MDI0_P") (class "Default")
      (node (ref "RJ1") (pin "R1") (pinfunction "TD1+_R1") (pintype "unspecified"))
      (node (ref "U8") (pin "13") (pinfunction "MDIP0_13") (pintype "unspecified"))
    )
    (net (code "14") (name "ETH_MDI1_N") (class "Default")
      (node (ref "RJ1") (pin "R4") (pinfunction "TD2-_R4") (pintype "unspecified"))
      (node (ref "U8") (pin "18") (pinfunction "MDIN1_18") (pintype "unspecified"))
    )
    (net (code "15") (name "ETH_MDI1_P") (class "Default")
      (node (ref "RJ1") (pin "R3") (pinfunction "TD2+_R3") (pintype "unspecified"))
      (node (ref "U8") (pin "17") (pinfunction "MDIP1_17") (pintype "unspecified"))
    )
    (net (code "16") (name "ETH_MDI2_N") (class "Default")
      (node (ref "RJ1") (pin "R8") (pinfunction "TD3-_R8") (pintype "unspecified"))
      (node (ref "U8") (pin "21") (pinfunction "MDIN2_21") (pintype "unspecified"))
    )
    (net (code "17") (name "ETH_MDI2_P") (class "Default")
      (node (ref "RJ1") (pin "R7") (pinfunction "TD3+_R7") (pintype "unspecified"))
      (node (ref "U8") (pin "20") (pinfunction "MDIP2_20") (pintype "unspecified"))
    )
    (net (code "18") (name "ETH_MDI3_N") (class "Default")
      (node (ref "RJ1") (pin "R9") (pinfunction "TD4+_R9") (pintype "unspecified"))
      (node (ref "U8") (pin "24") (pinfunction "MDIN3_24") (pintype "unspecified"))
    )
    (net (code "19") (name "ETH_MDI3_P") (class "Default")
      (node (ref "RJ1") (pin "R10") (pinfunction "TD4-_R10") (pintype "unspecified"))
      (node (ref "U8") (pin "23") (pinfunction "MDIP3_23") (pintype "unspecified"))
    )
    (net (code "20") (name "ETH_RST_N") (class "Default")
      (node (ref "R10") (pin "2") (pinfunction "2_2") (pintype "input"))
      (node (ref "U8") (pin "36") (pinfunction "PERSTB_36") (pintype "unspecified"))
    )
    (net (code "21") (name "ETH_RX_N") (class "Default")
      (node (ref "C56") (pin "2") (pinfunction "2_2") (pintype "unspecified"))
    )
    (net (code "22") (name "ETH_RX_P") (class "Default")
      (node (ref "C1") (pin "2") (pinfunction "2_2") (pintype "unspecified"))
      (node (ref "C10") (pin "2") (pinfunction "2_2") (pintype "unspecified"))
      (node (ref "C11") (pin "2") (pinfunction "2_2") (pintype "unspecified"))
      (node (ref "C12") (pin "2") (pinfunction "2_2") (pintype "unspecified"))
      (node (ref "C27") (pin "1") (pinfunction "1_1") (pintype "unspecified"))
      (node (ref "C28") (pin "1") (pinfunction "1_1") (pintype "unspecified"))
      (node (ref "C29") (pin "2") (pinfunction "2_2") (pintype "unspecified"))
      (node (ref "C3") (pin "2") (pinfunction "2_2") (pintype "unspecified"))
      (node (ref "C30") (pin "1") (pinfunction "1_1") (pintype "unspecified"))
      (node (ref "C31") (pin "2") (pinfunction "2_2") (pintype "unspecified"))
      (node (ref "C32") (pin "1") (pinfunction "1_1") (pintype "unspecified"))
      (node (ref "C35") (pin "1") (pinfunction "1_1") (pintype "unspecified"))
      (node (ref "C36") (pin "1") (pinfunction "1_1") (pintype "unspecified"))
      (node (ref "C37") (pin "1") (pinfunction "1_1") (pintype "unspecified"))
      (node (ref "C4") (pin "2") (pinfunction "2_2") (pintype "unspecified"))
      (node (ref "C43") (pin "2") (pinfunction "2_2") (pintype "unspecified"))
      (node (ref "C5") (pin "2") (pinfunction "2_2") (pintype "unspecified"))
      (node (ref "C53") (pin "2") (pinfunction "2_2") (pintype "unspecified"))
      (node (ref "C54") (pin "1") (pinfunction "1_1") (pintype "unspecified"))
      (node (ref "C55") (pin "1") (pinfunction "1_1") (pintype "unspecified"))
      (node (ref "C57") (pin "2") (pinfunction "2_2") (pintype "unspecified"))
      (node (ref "C58") (pin "2") (pinfunction "2_2") (pintype "unspecified"))
      (node (ref "C59") (pin "1") (pinfunction "1_1") (pintype "unspecified"))
      (node (ref "C6") (pin "2") (pinfunction "2_2") (pintype "unspecified"))
      (node (ref "C60") (pin "1") (pinfunction "1_1") (pintype "unspecified"))
      (node (ref "C61") (pin "1") (pinfunction "1_1") (pintype "unspecified"))
      (node (ref "C62") (pin "1") (pinfunction "1_1") (pintype "unspecified"))
      (node (ref "C63") (pin "1") (pinfunction "1_1") (pintype "unspecified"))
      (node (ref "C64") (pin "2") (pinfunction "2_2") (pintype "unspecified"))
      (node (ref "C65") (pin "2") (pinfunction "2_2") (pintype "unspecified"))
      (node (ref "C66") (pin "2") (pinfunction "2_2") (pintype "unspecified"))
      (node (ref "C67") (pin "2") (pinfunction "2_2") (pintype "unspecified"))
      (node (ref "C68") (pin "2") (pinfunction "2_2") (pintype "unspecified"))
      (node (ref "C69") (pin "2") (pinfunction "2_2") (pintype "unspecified"))
      (node (ref "C70") (pin "2") (pinfunction "2_2") (pintype "unspecified"))
      (node (ref "C71") (pin "2") (pinfunction "2_2") (pintype "unspecified"))
      (node (ref "C72") (pin "1") (pinfunction "1_1") (pintype "unspecified"))
      (node (ref "C8") (pin "2") (pinfunction "2_2") (pintype "unspecified"))
      (node (ref "C9") (pin "2") (pinfunction "2_2") (pintype "unspecified"))
      (node (ref "CN1") (pin "1") (pinfunction "S1_1") (pintype "unspecified"))
      (node (ref "CN1") (pin "11") (pinfunction "P4_11") (pintype "unspecified"))
      (node (ref "CN1") (pin "12") (pinfunction "P5_12") (pintype "unspecified"))
      (node (ref "CN1") (pin "13") (pinfunction "P6_13") (pintype "unspecified"))
      (node (ref "CN1") (pin "17") (pinfunction "P10_17") (pintype "unspecified"))
      (node (ref "CN1") (pin "18") (pinfunction "P11_18") (pintype "unspecified"))
      (node (ref "CN1") (pin "19") (pinfunction "P12_19") (pintype "unspecified"))
      (node (ref "CN1") (pin "23") (pinfunction "SHELL_23") (pintype "unspecified"))
      (node (ref "CN1") (pin "24") (pinfunction "SHELL_24") (pintype "unspecified"))
      (node (ref "CN1") (pin "4") (pinfunction "S4_4") (pintype "unspecified"))
      (node (ref "CN1") (pin "7") (pinfunction "S7_7") (pintype "unspecified"))
      (node (ref "CN2") (pin "1") (pinfunction "S1_1") (pintype "unspecified"))
      (node (ref "CN2") (pin "11") (pinfunction "P4_11") (pintype "unspecified"))
      (node (ref "CN2") (pin "12") (pinfunction "P5_12") (pintype "unspecified"))
      (node (ref "CN2") (pin "13") (pinfunction "P6_13") (pintype "unspecified"))
      (node (ref "CN2") (pin "17") (pinfunction "P10_17") (pintype "unspecified"))
      (node (ref "CN2") (pin "18") (pinfunction "P11_18") (pintype "unspecified"))
      (node (ref "CN2") (pin "19") (pinfunction "P12_19") (pintype "unspecified"))
      (node (ref "CN2") (pin "23") (pinfunction "SHELL_23") (pintype "unspecified"))
      (node (ref "CN2") (pin "24") (pinfunction "SHELL_24") (pintype "unspecified"))
      (node (ref "CN2") (pin "4") (pinfunction "S4_4") (pintype "unspecified"))
      (node (ref "CN2") (pin "7") (pinfunction "S7_7") (pintype "unspecified"))
      (node (ref "DC1") (pin "2") (pinfunction "2_2") (pintype "unspecified"))
      (node (ref "DC1") (pin "3") (pinfunction "3_3") (pintype "unspecified"))
      (node (ref "DC1") (pin "5") (pinfunction "5_5") (pintype "unspecified"))
      (node (ref "R23") (pin "1") (pinfunction "1_1") (pintype "unspecified"))
      (node (ref "R25") (pin "2") (pinfunction "2_2") (pintype "unspecified"))
      (node (ref "R4") (pin "1") (pinfunction "1_1") (pintype "unspecified"))
      (node (ref "R6") (pin "1") (pinfunction "1_1") (pintype "unspecified"))
      (node (ref "R7") (pin "1") (pinfunction "1_1") (pintype "unspecified"))
      (node (ref "R8") (pin "1") (pinfunction "1_1") (pintype "unspecified"))
      (node (ref "RJ1") (pin "1") (pinfunction "GND_1") (pintype "unspecified"))
      (node (ref "RJ1") (pin "2") (pinfunction "GND_2") (pintype "unspecified"))
      (node (ref "U1") (pin "7") (pinfunction "GND_7") (pintype "unspecified"))
      (node (ref "U1") (pin "9") (pinfunction "EP_9") (pintype "unspecified"))
      (node (ref "U5") (pin "7") (pinfunction "GND_7") (pintype "unspecified"))
      (node (ref "U5") (pin "9") (pinfunction "EP_9") (pintype "unspecified"))
      (node (ref "U6") (pin "1") (pinfunction "1_1") (pintype "unspecified"))
      (node (ref "U6") (pin "33") (pinfunction "33_33") (pintype "unspecified"))
      (node (ref "U6") (pin "39") (pinfunction "39_39") (pintype "unspecified"))
      (node (ref "U6") (pin "45") (pinfunction "45_45") (pintype "unspecified"))
      (node (ref "U6") (pin "51") (pinfunction "51_51") (pintype "unspecified"))
      (node (ref "U6") (pin "57") (pinfunction "57_57") (pintype "unspecified"))
      (node (ref "U6") (pin "63") (pinfunction "63_63") (pintype "unspecified"))
      (node (ref "U6") (pin "69") (pinfunction "69_69") (pintype "unspecified"))
      (node (ref "U6") (pin "7") (pinfunction "7_7") (pintype "unspecified"))
      (node (ref "U6") (pin "75") (pinfunction "75_75") (pintype "unspecified"))
      (node (ref "U6") (pin "76") (pinfunction "76_76") (pintype "unspecified"))
      (node (ref "U6") (pin "77") (pinfunction "77_77") (pintype "unspecified"))
      (node (ref "U7") (pin "1") (pinfunction "1_1") (pintype "unspecified"))
      (node (ref "U7") (pin "15") (pinfunction "15_15") (pintype "unspecified"))
      (node (ref "U7") (pin "21") (pinfunction "21_21") (pintype "unspecified"))
      (node (ref "U7") (pin "27") (pinfunction "27_27") (pintype "unspecified"))
      (node (ref "U7") (pin "3") (pinfunction "3_3") (pintype "unspecified"))
      (node (ref "U7") (pin "33") (pinfunction "33_33") (pintype "unspecified"))
      (node (ref "U7") (pin "39") (pinfunction "39_39") (pintype "unspecified"))
      (node (ref "U7") (pin "45") (pinfunction "45_45") (pintype "unspecified"))
      (node (ref "U7") (pin "51") (pinfunction "51_51") (pintype "unspecified"))
      (node (ref "U7") (pin "57") (pinfunction "57_57") (pintype "unspecified"))
      (node (ref "U7") (pin "71") (pinfunction "71_71") (pintype "unspecified"))
      (node (ref "U7") (pin "73") (pinfunction "73_73") (pintype "unspecified"))
      (node (ref "U7") (pin "75") (pinfunction "75_75") (pintype "unspecified"))
      (node (ref "U7") (pin "76") (pinfunction "76_76") (pintype "unspecified"))
      (node (ref "U7") (pin "77") (pinfunction "77_77") (pintype "unspecified"))
      (node (ref "U7") (pin "9") (pinfunction "9_9") (pintype "unspecified"))
      (node (ref "U8") (pin "40") (pinfunction "GND_40") (pintype "unspecified"))
      (node (ref "U8") (pin "49") (pinfunction "GND_49") (pintype "unspecified"))
      (node (ref "U9") (pin "2") (pinfunction "GND_2") (pintype "unspecified"))
    )
    (net (code "23") (name "ETH_TX_N") (class "Default")
      (node (ref "U8") (pin "42") (pinfunction "HSIN_42") (pintype "unspecified"))
    )
    (net (code "24") (name "ETH_TX_P") (class "Default")
      (node (ref "U8") (pin "41") (pinfunction "HSIP_41") (pintype "unspecified"))
    )
    (net (code "25") (name "ETH_WAKE_N") (class "Default")
      (node (ref "R19") (pin "2") (pinfunction "2_2") (pintype "unspecified"))
      (node (ref "U8") (pin "2") (pinfunction "LANWAKEB_2") (pintype "unspecified"))
    )
    (net (code "26") (name "LED0") (class "Default")
      (node (ref "R21") (pin "2") (pinfunction "2_2") (pintype "input"))
      (node (ref "U8") (pin "30") (pinfunction "LED0/EEDI/SPISI/SDA_30") (pintype "unspecified"))
    )
    (net (code "27") (name "LED2") (class "Default")
      (node (ref "R20") (pin "1") (pinfunction "1_1") (pintype "input"))
      (node (ref "U8") (pin "25") (pinfunction "LED2/EEDO/SPIS0_25") (pintype "unspecified"))
    )
    (net (code "28") (name "NVME_CLKREQ_N") (class "Default")
      (node (ref "R15") (pin "1") (pinfunction "1_1") (pintype "unspecified"))
      (node (ref "U7") (pin "52") (pinfunction "52_52") (pintype "unspecified"))
    )
    (net (code "29") (name "NVME_CLK_N") (class "Default")
      (node (ref "U7") (pin "53") (pinfunction "53_53") (pintype "unspecified"))
    )
    (net (code "30") (name "NVME_CLK_P") (class "Default")
      (node (ref "U7") (pin "55") (pinfunction "55_55") (pintype "unspecified"))
    )
    (net (code "31") (name "NVME_RST_N") (class "Default")
      (node (ref "C43") (pin "1") (pinfunction "1_1") (pintype "unspecified"))
      (node (ref "R14") (pin "1") (pinfunction "1_1") (pintype "unspecified"))
      (node (ref "U7") (pin "50") (pinfunction "50_50") (pintype "unspecified"))
    )
    (net (code "32") (name "NVME_RX0_N") (class "Default")
      (node (ref "U7") (pin "47") (pinfunction "47_47") (pintype "unspecified"))
    )
    (net (code "33") (name "NVME_RX0_P") (class "Default")
      (node (ref "U7") (pin "49") (pinfunction "49_49") (pintype "unspecified"))
    )
    (net (code "34") (name "NVME_RX1_N") (class "Default")
      (node (ref "U7") (pin "35") (pinfunction "35_35") (pintype "unspecified"))
    )
    (net (code "35") (name "NVME_RX1_P") (class "Default")
      (node (ref "U7") (pin "37") (pinfunction "37_37") (pintype "unspecified"))
    )
    (net (code "36") (name "NVME_RX2_N") (class "Default")
      (node (ref "U7") (pin "23") (pinfunction "23_23") (pintype "unspecified"))
    )
    (net (code "37") (name "NVME_RX2_P") (class "Default")
      (node (ref "U7") (pin "25") (pinfunction "25_25") (pintype "unspecified"))
    )
    (net (code "38") (name "NVME_RX3_N") (class "Default")
      (node (ref "U7") (pin "11") (pinfunction "11_11") (pintype "unspecified"))
    )
    (net (code "39") (name "NVME_RX3_P") (class "Default")
      (node (ref "U7") (pin "13") (pinfunction "13_13") (pintype "unspecified"))
    )
    (net (code "40") (name "NVME_TX0_N") (class "Default")
      (node (ref "C50") (pin "1") (pinfunction "1_1") (pintype "unspecified"))
    )
    (net (code "41") (name "NVME_TX0_P") (class "Default")
      (node (ref "C51") (pin "1") (pinfunction "1_1") (pintype "unspecified"))
    )
    (net (code "42") (name "NVME_TX1_N") (class "Default")
      (node (ref "C48") (pin "1") (pinfunction "1_1") (pintype "unspecified"))
    )
    (net (code "43") (name "NVME_TX1_P") (class "Default")
      (node (ref "C49") (pin "1") (pinfunction "1_1") (pintype "unspecified"))
    )
    (net (code "44") (name "NVME_TX2_N") (class "Default")
      (node (ref "C46") (pin "1") (pinfunction "1_1") (pintype "unspecified"))
    )
    (net (code "45") (name "NVME_TX2_P") (class "Default")
      (node (ref "C47") (pin "1") (pinfunction "1_1") (pintype "unspecified"))
    )
    (net (code "46") (name "NVME_TX3_N") (class "Default")
      (node (ref "C44") (pin "1") (pinfunction "1_1") (pintype "unspecified"))
    )
    (net (code "47") (name "NVME_TX3_P") (class "Default")
      (node (ref "C45") (pin "1") (pinfunction "1_1") (pintype "unspecified"))
    )
    (net (code "48") (name "NVME_WAKE_N") (class "Default")
      (node (ref "R16") (pin "1") (pinfunction "1_1") (pintype "unspecified"))
      (node (ref "U7") (pin "54") (pinfunction "54_54") (pintype "unspecified"))
    )
    (net (code "49") (name "Net-(C1-Pad1)") (class "Default")
      (node (ref "C1") (pin "1") (pinfunction "1_1") (pintype "unspecified"))
      (node (ref "R2") (pin "2") (pinfunction "2_2") (pintype "unspecified"))
    )
    (net (code "50") (name "Net-(C8-Pad1)") (class "Default")
      (node (ref "C8") (pin "1") (pinfunction "1_1") (pintype "unspecified"))
      (node (ref "R5") (pin "2") (pinfunction "2_2") (pintype "input"))
    )
    (net (code "51") (name "Net-(C33-Pad1)") (class "Default")
      (node (ref "C33") (pin "1") (pinfunction "1_1") (pintype "unspecified"))
      (node (ref "U6") (pin "41") (pinfunction "41_41") (pintype "unspecified"))
    )
    (net (code "52") (name "Net-(C34-Pad1)") (class "Default")
      (node (ref "C34") (pin "1") (pinfunction "1_1") (pintype "unspecified"))
      (node (ref "U6") (pin "43") (pinfunction "43_43") (pintype "unspecified"))
    )
    (net (code "53") (name "Net-(C38-Pad1)") (class "Default")
      (node (ref "C38") (pin "1") (pinfunction "1_1") (pintype "input"))
      (node (ref "U7") (pin "2") (pinfunction "2_2") (pintype "unspecified"))
    )
    (net (code "54") (name "Net-(C39-Pad1)") (class "Default")
      (node (ref "C39") (pin "1") (pinfunction "1_1") (pintype "input"))
      (node (ref "U7") (pin "4") (pinfunction "4_4") (pintype "unspecified"))
    )
    (net (code "55") (name "Net-(C40-Pad1)") (class "Default")
      (node (ref "C40") (pin "1") (pinfunction "1_1") (pintype "input"))
      (node (ref "U7") (pin "70") (pinfunction "70_70") (pintype "unspecified"))
    )
    (net (code "56") (name "Net-(C41-Pad1)") (class "Default")
      (node (ref "C41") (pin "1") (pinfunction "1_1") (pintype "input"))
      (node (ref "U7") (pin "72") (pinfunction "72_72") (pintype "unspecified"))
    )
    (net (code "57") (name "Net-(C42-Pad1)") (class "Default")
      (node (ref "C42") (pin "1") (pinfunction "1_1") (pintype "input"))
      (node (ref "U7") (pin "74") (pinfunction "74_74") (pintype "unspecified"))
    )
    (net (code "58") (name "Net-(C44-Pad2)") (class "Default")
      (node (ref "C44") (pin "2") (pinfunction "2_2") (pintype "unspecified"))
      (node (ref "U7") (pin "5") (pinfunction "5_5") (pintype "unspecified"))
    )
    (net (code "59") (name "Net-(C45-Pad2)") (class "Default")
      (node (ref "C45") (pin "2") (pinfunction "2_2") (pintype "unspecified"))
      (node (ref "U7") (pin "7") (pinfunction "7_7") (pintype "unspecified"))
    )
    (net (code "60") (name "Net-(C46-Pad2)") (class "Default")
      (node (ref "C46") (pin "2") (pinfunction "2_2") (pintype "unspecified"))
      (node (ref "U7") (pin "17") (pinfunction "17_17") (pintype "unspecified"))
    )
    (net (code "61") (name "Net-(C47-Pad2)") (class "Default")
      (node (ref "C47") (pin "2") (pinfunction "2_2") (pintype "unspecified"))
      (node (ref "U7") (pin "19") (pinfunction "19_19") (pintype "unspecified"))
    )
    (net (code "62") (name "Net-(C48-Pad2)") (class "Default")
      (node (ref "C48") (pin "2") (pinfunction "2_2") (pintype "unspecified"))
      (node (ref "U7") (pin "29") (pinfunction "29_29") (pintype "unspecified"))
    )
    (net (code "63") (name "Net-(C49-Pad2)") (class "Default")
      (node (ref "C49") (pin "2") (pinfunction "2_2") (pintype "unspecified"))
      (node (ref "U7") (pin "31") (pinfunction "31_31") (pintype "unspecified"))
    )
    (net (code "64") (name "Net-(C50-Pad2)") (class "Default")
      (node (ref "C50") (pin "2") (pinfunction "2_2") (pintype "unspecified"))
      (node (ref "U7") (pin "41") (pinfunction "41_41") (pintype "unspecified"))
    )
    (net (code "65") (name "Net-(C51-Pad2)") (class "Default")
      (node (ref "C51") (pin "2") (pinfunction "2_2") (pintype "unspecified"))
      (node (ref "U7") (pin "43") (pinfunction "43_43") (pintype "unspecified"))
    )
    (net (code "66") (name "Net-(CN1-P7)") (class "Default")
      (node (ref "C15") (pin "1") (pinfunction "1_1") (pintype "unspecified"))
      (node (ref "CN1") (pin "14") (pinfunction "P7_14") (pintype "unspecified"))
    )
    (net (code "67") (name "Net-(CN1-P8)") (class "Default")
      (node (ref "C14") (pin "1") (pinfunction "1_1") (pintype "unspecified"))
      (node (ref "CN1") (pin "15") (pinfunction "P8_15") (pintype "unspecified"))
    )
    (net (code "68") (name "Net-(CN1-P9)") (class "Default")
      (node (ref "C13") (pin "1") (pinfunction "1_1") (pintype "unspecified"))
      (node (ref "CN1") (pin "16") (pinfunction "P9_16") (pintype "unspecified"))
    )
    (net (code "69") (name "Net-(CN1-S2)") (class "Default")
      (node (ref "C19") (pin "1") (pinfunction "1_1") (pintype "unspecified"))
      (node (ref "CN1") (pin "2") (pinfunction "S2_2") (pintype "unspecified"))
    )
    (net (code "70") (name "Net-(CN1-S3)") (class "Default")
      (node (ref "C18") (pin "1") (pinfunction "1_1") (pintype "unspecified"))
      (node (ref "CN1") (pin "3") (pinfunction "S3_3") (pintype "unspecified"))
    )
    (net (code "71") (name "Net-(CN1-S5)") (class "Default")
      (node (ref "C17") (pin "1") (pinfunction "1_1") (pintype "unspecified"))
      (node (ref "CN1") (pin "5") (pinfunction "S5_5") (pintype "unspecified"))
    )
    (net (code "72") (name "Net-(CN1-S6)") (class "Default")
      (node (ref "C16") (pin "1") (pinfunction "1_1") (pintype "unspecified"))
      (node (ref "CN1") (pin "6") (pinfunction "S6_6") (pintype "unspecified"))
    )
    (net (code "73") (name "Net-(CN2-P7)") (class "Default")
      (node (ref "C24") (pin "1") (pinfunction "1_1") (pintype "unspecified"))
      (node (ref "CN2") (pin "14") (pinfunction "P7_14") (pintype "unspecified"))
    )
    (net (code "74") (name "Net-(CN2-P8)") (class "Default")
      (node (ref "C25") (pin "1") (pinfunction "1_1") (pintype "unspecified"))
      (node (ref "CN2") (pin "15") (pinfunction "P8_15") (pintype "unspecified"))
    )
    (net (code "75") (name "Net-(CN2-P9)") (class "Default")
      (node (ref "C26") (pin "1") (pinfunction "1_1") (pintype "unspecified"))
      (node (ref "CN2") (pin "16") (pinfunction "P9_16") (pintype "unspecified"))
    )
    (net (code "76") (name "Net-(CN2-S2)") (class "Default")
      (node (ref "C23") (pin "1") (pinfunction "1_1") (pintype "unspecified"))
      (node (ref "CN2") (pin "2") (pinfunction "S2_2") (pintype "unspecified"))
    )
    (net (code "77") (name "Net-(CN2-S3)") (class "Default")
      (node (ref "C22") (pin "1") (pinfunction "1_1") (pintype "unspecified"))
      (node (ref "CN2") (pin "3") (pinfunction "S3_3") (pintype "unspecified"))
    )
    (net (code "78") (name "Net-(CN2-S5)") (class "Default")
      (node (ref "C21") (pin "1") (pinfunction "1_1") (pintype "unspecified"))
      (node (ref "CN2") (pin "5") (pinfunction "S5_5") (pintype "unspecified"))
    )
    (net (code "79") (name "Net-(CN2-S6)") (class "Default")
      (node (ref "C20") (pin "1") (pinfunction "1_1") (pintype "unspecified"))
      (node (ref "CN2") (pin "6") (pinfunction "S6_6") (pintype "unspecified"))
    )
    (net (code "80") (name "Net-(RJ1-LED_G-O+)") (class "Default")
      (node (ref "R20") (pin "2") (pinfunction "2_2") (pintype "input"))
      (node (ref "RJ1") (pin "L1") (pinfunction "LED_G-O+_L1") (pintype "unspecified"))
    )
    (net (code "81") (name "Net-(RJ1-LED_Y-)") (class "Default")
      (node (ref "R21") (pin "1") (pinfunction "1_1") (pintype "input"))
      (node (ref "RJ1") (pin "L3") (pinfunction "LED_Y-_L3") (pintype "unspecified"))
    )
    (net (code "82") (name "Net-(U1-BST)") (class "Default")
      (node (ref "C2") (pin "1") (pinfunction "1_1") (pintype "unspecified"))
      (node (ref "U1") (pin "1") (pinfunction "BST_1") (pintype "unspecified"))
    )
    (net (code "83") (name "Net-(U1-COMP)") (class "Default")
      (node (ref "R2") (pin "1") (pinfunction "1_1") (pintype "unspecified"))
      (node (ref "U1") (pin "6") (pinfunction "COMP_6") (pintype "unspecified"))
    )
    (net (code "84") (name "Net-(U1-EN)") (class "Default")
      (node (ref "R1") (pin "2") (pinfunction "2_2") (pintype "unspecified"))
      (node (ref "U1") (pin "3") (pinfunction "EN_3") (pintype "unspecified"))
    )
    (net (code "85") (name "Net-(U1-FB)") (class "Default")
      (node (ref "R3") (pin "2") (pinfunction "2_2") (pintype "unspecified"))
      (node (ref "R4") (pin "2") (pinfunction "2_2") (pintype "unspecified"))
      (node (ref "U1") (pin "5") (pinfunction "FB_5") (pintype "unspecified"))
    )
    (net (code "86") (name "Net-(U1-RT{slash}CLK)") (class "Default")
      (node (ref "R6") (pin "2") (pinfunction "2_2") (pintype "unspecified"))
      (node (ref "U1") (pin "4") (pinfunction "RT/CLK_4") (pintype "unspecified"))
    )
    (net (code "87") (name "Net-(U1-SW)") (class "Default")
      (node (ref "C2") (pin "2") (pinfunction "2_2") (pintype "unspecified"))
      (node (ref "U1") (pin "8") (pinfunction "SW_8") (pintype "unspecified"))
      (node (ref "U2") (pin "1") (pinfunction "1_1") (pintype "unspecified"))
    )
    (net (code "88") (name "Net-(U5-BST)") (class "Default")
      (node (ref "C7") (pin "1") (pinfunction "1_1") (pintype "unspecified"))
      (node (ref "U5") (pin "1") (pinfunction "BST_1") (pintype "unspecified"))
    )
    (net (code "89") (name "Net-(U5-COMP)") (class "Default")
      (node (ref "R5") (pin "1") (pinfunction "1_1") (pintype "input"))
      (node (ref "U5") (pin "6") (pinfunction "COMP_6") (pintype "unspecified"))
    )
    (net (code "90") (name "Net-(U5-EN)") (class "Default")
      (node (ref "R11") (pin "2") (pinfunction "2_2") (pintype "unspecified"))
      (node (ref "U5") (pin "3") (pinfunction "EN_3") (pintype "unspecified"))
    )
    (net (code "91") (name "Net-(U5-FB)") (class "Default")
      (node (ref "R8") (pin "2") (pinfunction "2_2") (pintype "unspecified"))
      (node (ref "U3") (pin "1") (pinfunction "1_1") (pintype "unspecified"))
      (node (ref "U5") (pin "5") (pinfunction "FB_5") (pintype "unspecified"))
    )
    (net (code "92") (name "Net-(U5-RT{slash}CLK)") (class "Default")
      (node (ref "R7") (pin "2") (pinfunction "2_2") (pintype "unspecified"))
      (node (ref "U5") (pin "4") (pinfunction "RT/CLK_4") (pintype "unspecified"))
    )
    (net (code "93") (name "Net-(U5-SW)") (class "Default")
      (node (ref "C7") (pin "2") (pinfunction "2_2") (pintype "unspecified"))
      (node (ref "U4") (pin "1") (pinfunction "1_1") (pintype "unspecified"))
      (node (ref "U5") (pin "8") (pinfunction "SW_8") (pintype "unspecified"))
    )
    (net (code "94") (name "Net-(U8-HSON)") (class "Default")
      (node (ref "C56") (pin "1") (pinfunction "1_1") (pintype "unspecified"))
      (node (ref "U8") (pin "39") (pinfunction "HSON_39") (pintype "unspecified"))
    )
    (net (code "95") (name "Net-(U8-HSOP)") (class "Default")
      (node (ref "C57") (pin "1") (pinfunction "1_1") (pintype "unspecified"))
      (node (ref "U8") (pin "38") (pinfunction "HSOP_38") (pintype "unspecified"))
    )
    (net (code "96") (name "Net-(U8-ISOLATEB)") (class "Default")
      (node (ref "R18") (pin "1") (pinfunction "1_1") (pintype "input"))
      (node (ref "U8") (pin "1") (pinfunction "ISOLATEB_1") (pintype "unspecified"))
    )
    (net (code "97") (name "Net-(U8-LED1{slash}EESK{slash}SPISC)") (class "Default")
      (node (ref "R22") (pin "1") (pinfunction "1_1") (pintype "input"))
      (node (ref "U8") (pin "27") (pinfunction "LED1/EESK/SPISC_27") (pintype "unspecified"))
    )
    (net (code "98") (name "Net-(U8-RSET)") (class "Default")
      (node (ref "R23") (pin "2") (pinfunction "2_2") (pintype "unspecified"))
      (node (ref "U8") (pin "12") (pinfunction "RSET_12") (pintype "unspecified"))
    )
    (net (code "99") (name "Net-(U9-FB)") (class "Default")
      (node (ref "R24") (pin "1") (pinfunction "1_1") (pintype "unspecified"))
      (node (ref "R25") (pin "1") (pinfunction "1_1") (pintype "unspecified"))
      (node (ref "U9") (pin "1") (pinfunction "FB_1") (pintype "unspecified"))
    )
    (net (code "100") (name "Net-(U9-SW)") (class "Default")
      (node (ref "L3") (pin "1") (pinfunction "1_1") (pintype "unspecified"))
      (node (ref "U9") (pin "4") (pinfunction "SW_4") (pintype "unspecified"))
    )
    (net (code "101") (name "Net-(X1-GND)") (class "Default")
      (node (ref "C52") (pin "1") (pinfunction "1_1") (pintype "unspecified"))
      (node (ref "X1") (pin "2") (pinfunction "GND_2") (pintype "unspecified"))
    )
    (net (code "102") (name "POWEXT") (class "Default")
      (node (ref "U8") (pin "6") (pinfunction "POW_EXT_SWR_6") (pintype "unspecified"))
      (node (ref "U9") (pin "5") (pinfunction "EN_5") (pintype "unspecified"))
    )
    (net (code "103") (name "SATA0_RX_N") (class "Default")
      (node (ref "C17") (pin "2") (pinfunction "2_2") (pintype "unspecified"))
    )
    (net (code "104") (name "SATA0_RX_P") (class "Default")
      (node (ref "C16") (pin "2") (pinfunction "2_2") (pintype "unspecified"))
    )
    (net (code "105") (name "SATA0_TX_N") (class "Default")
      (node (ref "C18") (pin "2") (pinfunction "2_2") (pintype "unspecified"))
    )
    (net (code "106") (name "SATA0_TX_P") (class "Default")
      (node (ref "C19") (pin "2") (pinfunction "2_2") (pintype "unspecified"))
    )
    (net (code "107") (name "SATA1_RX_N") (class "Default")
      (node (ref "C21") (pin "2") (pinfunction "2_2") (pintype "unspecified"))
    )
    (net (code "108") (name "SATA1_RX_P") (class "Default")
      (node (ref "C20") (pin "2") (pinfunction "2_2") (pintype "unspecified"))
    )
    (net (code "109") (name "SATA1_TX_N") (class "Default")
      (node (ref "C22") (pin "2") (pinfunction "2_2") (pintype "unspecified"))
    )
    (net (code "110") (name "SATA1_TX_P") (class "Default")
      (node (ref "C23") (pin "2") (pinfunction "2_2") (pintype "unspecified"))
    )
    (net (code "111") (name "VCC_ETH") (class "Default")
      (node (ref "C52") (pin "2") (pinfunction "2_2") (pintype "unspecified"))
      (node (ref "C53") (pin "1") (pinfunction "1_1") (pintype "unspecified"))
      (node (ref "C54") (pin "2") (pinfunction "2_2") (pintype "unspecified"))
      (node (ref "C55") (pin "2") (pinfunction "2_2") (pintype "unspecified"))
      (node (ref "C60") (pin "2") (pinfunction "2_2") (pintype "unspecified"))
      (node (ref "C62") (pin "2") (pinfunction "2_2") (pintype "unspecified"))
      (node (ref "C65") (pin "1") (pinfunction "1_1") (pintype "unspecified"))
      (node (ref "C66") (pin "1") (pinfunction "1_1") (pintype "unspecified"))
      (node (ref "C68") (pin "1") (pinfunction "1_1") (pintype "unspecified"))
      (node (ref "C69") (pin "1") (pinfunction "1_1") (pintype "unspecified"))
      (node (ref "C70") (pin "1") (pinfunction "1_1") (pintype "unspecified"))
      (node (ref "L2") (pin "1") (pinfunction "1_1") (pintype "unspecified"))
      (node (ref "R10") (pin "1") (pinfunction "1_1") (pintype "input"))
      (node (ref "R17") (pin "2") (pinfunction "2_2") (pintype "input"))
      (node (ref "R18") (pin "2") (pinfunction "2_2") (pintype "input"))
      (node (ref "R19") (pin "1") (pinfunction "1_1") (pintype "unspecified"))
      (node (ref "R22") (pin "2") (pinfunction "2_2") (pintype "input"))
      (node (ref "RJ1") (pin "L2") (pinfunction "LED_G+O-_L2") (pintype "unspecified"))
      (node (ref "RJ1") (pin "L4") (pinfunction "LED_Y+_L4") (pintype "unspecified"))
      (node (ref "RJ1") (pin "R5") (pinfunction "CT_R5") (pintype "unspecified"))
      (node (ref "RJ1") (pin "R6") (pinfunction "CT_R6") (pintype "unspecified"))
      (node (ref "U8") (pin "15") (pinfunction "AVDD33_15") (pintype "unspecified"))
      (node (ref "U8") (pin "19") (pinfunction "AVDD33_19") (pintype "unspecified"))
      (node (ref "U8") (pin "29") (pinfunction "DVDD33_29") (pintype "unspecified"))
      (node (ref "U8") (pin "33") (pinfunction "AVDD33_33") (pintype "unspecified"))
      (node (ref "U8") (pin "34") (pinfunction "AVDD33_XTAL_34") (pintype "unspecified"))
      (node (ref "U8") (pin "43") (pinfunction "EVDD33_43") (pintype "unspecified"))
      (node (ref "U8") (pin "46") (pinfunction "DVDD33_46") (pintype "unspecified"))
      (node (ref "X1") (pin "1") (pinfunction "ENABLE_CONTROL_1") (pintype "unspecified"))
      (node (ref "X1") (pin "4") (pinfunction "VDD_4") (pintype "unspecified"))
    )
    (net (code "112") (name "WIFI_CLKREQ_N") (class "Default")
      (node (ref "R12") (pin "2") (pinfunction "2_2") (pintype "unspecified"))
      (node (ref "U6") (pin "53") (pinfunction "53_53") (pintype "unspecified"))
    )
    (net (code "113") (name "WIFI_CLK_N") (class "Default")
      (node (ref "U6") (pin "49") (pinfunction "49_49") (pintype "unspecified"))
    )
    (net (code "114") (name "WIFI_CLK_P") (class "Default")
      (node (ref "U6") (pin "47") (pinfunction "47_47") (pintype "unspecified"))
    )
    (net (code "115") (name "WIFI_RST_N") (class "Default")
      (node (ref "C35") (pin "2") (pinfunction "2_2") (pintype "unspecified"))
      (node (ref "R9") (pin "1") (pinfunction "1_1") (pintype "unspecified"))
      (node (ref "U6") (pin "52") (pinfunction "52_52") (pintype "unspecified"))
    )
    (net (code "116") (name "WIFI_RX_N") (class "Default")
      (node (ref "U6") (pin "37") (pinfunction "37_37") (pintype "unspecified"))
    )
    (net (code "117") (name "WIFI_RX_P") (class "Default")
      (node (ref "U6") (pin "35") (pinfunction "35_35") (pintype "unspecified"))
    )
    (net (code "118") (name "WIFI_TX_N") (class "Default")
      (node (ref "C34") (pin "2") (pinfunction "2_2") (pintype "unspecified"))
    )
    (net (code "119") (name "WIFI_TX_P") (class "Default")
      (node (ref "C33") (pin "2") (pinfunction "2_2") (pintype "unspecified"))
    )
    (net (code "120") (name "WIFI_WAKE_N") (class "Default")
      (node (ref "R13") (pin "2") (pinfunction "2_2") (pintype "unspecified"))
      (node (ref "U6") (pin "55") (pinfunction "55_55") (pintype "unspecified"))
    )
    (net (code "121") (name "unconnected-(CN1-P1-Pad8)") (class "Default")
      (node (ref "CN1") (pin "8") (pinfunction "P1_8") (pintype "unspecified+no_connect"))
    )
    (net (code "122") (name "unconnected-(CN1-P2-Pad9)") (class "Default")
      (node (ref "CN1") (pin "9") (pinfunction "P2_9") (pintype "unspecified+no_connect"))
    )
    (net (code "123") (name "unconnected-(CN1-P3-Pad10)") (class "Default")
      (node (ref "CN1") (pin "10") (pinfunction "P3_10") (pintype "unspecified+no_connect"))
    )
    (net (code "124") (name "unconnected-(CN1-P5-Pad22)") (class "Default")
      (node (ref "CN1") (pin "22") (pinfunction "P5_22") (pintype "unspecified+no_connect"))
    )
    (net (code "125") (name "unconnected-(CN1-P13-Pad20)") (class "Default")
      (node (ref "CN1") (pin "20") (pinfunction "P13_20") (pintype "unspecified+no_connect"))
    )
    (net (code "126") (name "unconnected-(CN1-P14-Pad21)") (class "Default")
      (node (ref "CN1") (pin "21") (pinfunction "P14_21") (pintype "unspecified+no_connect"))
    )
    (net (code "127") (name "unconnected-(CN2-P1-Pad8)") (class "Default")
      (node (ref "CN2") (pin "8") (pinfunction "P1_8") (pintype "unspecified+no_connect"))
    )
    (net (code "128") (name "unconnected-(CN2-P2-Pad9)") (class "Default")
      (node (ref "CN2") (pin "9") (pinfunction "P2_9") (pintype "unspecified+no_connect"))
    )
    (net (code "129") (name "unconnected-(CN2-P3-Pad10)") (class "Default")
      (node (ref "CN2") (pin "10") (pinfunction "P3_10") (pintype "unspecified+no_connect"))
    )
    (net (code "130") (name "unconnected-(CN2-P5-Pad22)") (class "Default")
      (node (ref "CN2") (pin "22") (pinfunction "P5_22") (pintype "unspecified+no_connect"))
    )
    (net (code "131") (name "unconnected-(CN2-P13-Pad20)") (class "Default")
      (node (ref "CN2") (pin "20") (pinfunction "P13_20") (pintype "unspecified+no_connect"))
    )
    (net (code "132") (name "unconnected-(CN2-P14-Pad21)") (class "Default")
      (node (ref "CN2") (pin "21") (pinfunction "P14_21") (pintype "unspecified+no_connect"))
    )
    (net (code "133") (name "unconnected-(U6-Pad6)") (class "Default")
      (node (ref "U6") (pin "6") (pinfunction "6_6") (pintype "unspecified+no_connect"))
    )
    (net (code "134") (name "unconnected-(U6-Pad8)") (class "Default")
      (node (ref "U6") (pin "8") (pinfunction "8_8") (pintype "unspecified+no_connect"))
    )
    (net (code "135") (name "unconnected-(U6-Pad9)") (class "Default")
      (node (ref "U6") (pin "9") (pinfunction "9_9") (pintype "unspecified+no_connect"))
    )
    (net (code "136") (name "unconnected-(U6-Pad10)") (class "Default")
      (node (ref "U6") (pin "10") (pinfunction "10_10") (pintype "unspecified+no_connect"))
    )
    (net (code "137") (name "unconnected-(U6-Pad11)") (class "Default")
      (node (ref "U6") (pin "11") (pinfunction "11_11") (pintype "unspecified+no_connect"))
    )
    (net (code "138") (name "unconnected-(U6-Pad12)") (class "Default")
      (node (ref "U6") (pin "12") (pinfunction "12_12") (pintype "unspecified+no_connect"))
    )
    (net (code "139") (name "unconnected-(U6-Pad13)") (class "Default")
      (node (ref "U6") (pin "13") (pinfunction "13_13") (pintype "unspecified+no_connect"))
    )
    (net (code "140") (name "unconnected-(U6-Pad14)") (class "Default")
      (node (ref "U6") (pin "14") (pinfunction "14_14") (pintype "unspecified+no_connect"))
    )
    (net (code "141") (name "unconnected-(U6-Pad15)") (class "Default")
      (node (ref "U6") (pin "15") (pinfunction "15_15") (pintype "unspecified+no_connect"))
    )
    (net (code "142") (name "unconnected-(U6-Pad16)") (class "Default")
      (node (ref "U6") (pin "16") (pinfunction "16_16") (pintype "unspecified+no_connect"))
    )
    (net (code "143") (name "unconnected-(U6-Pad17)") (class "Default")
      (node (ref "U6") (pin "17") (pinfunction "17_17") (pintype "unspecified+no_connect"))
    )
    (net (code "144") (name "unconnected-(U6-Pad18)") (class "Default")
      (node (ref "U6") (pin "18") (pinfunction "18_18") (pintype "unspecified+no_connect"))
    )
    (net (code "145") (name "unconnected-(U6-Pad19)") (class "Default")
      (node (ref "U6") (pin "19") (pinfunction "19_19") (pintype "unspecified+no_connect"))
    )
    (net (code "146") (name "unconnected-(U6-Pad20)") (class "Default")
      (node (ref "U6") (pin "20") (pinfunction "20_20") (pintype "unspecified+no_connect"))
    )
    (net (code "147") (name "unconnected-(U6-Pad21)") (class "Default")
      (node (ref "U6") (pin "21") (pinfunction "21_21") (pintype "unspecified+no_connect"))
    )
    (net (code "148") (name "unconnected-(U6-Pad22)") (class "Default")
      (node (ref "U6") (pin "22") (pinfunction "22_22") (pintype "unspecified+no_connect"))
    )
    (net (code "149") (name "unconnected-(U6-Pad23)") (class "Default")
      (node (ref "U6") (pin "23") (pinfunction "23_23") (pintype "unspecified+no_connect"))
    )
    (net (code "150") (name "unconnected-(U6-Pad32)") (class "Default")
      (node (ref "U6") (pin "32") (pinfunction "32_32") (pintype "unspecified+no_connect"))
    )
    (net (code "151") (name "unconnected-(U6-Pad34)") (class "Default")
      (node (ref "U6") (pin "34") (pinfunction "34_34") (pintype "unspecified+no_connect"))
    )
    (net (code "152") (name "unconnected-(U6-Pad36)") (class "Default")
      (node (ref "U6") (pin "36") (pinfunction "36_36") (pintype "unspecified+no_connect"))
    )
    (net (code "153") (name "unconnected-(U6-Pad38)") (class "Default")
      (node (ref "U6") (pin "38") (pinfunction "38_38") (pintype "unspecified+no_connect"))
    )
    (net (code "154") (name "unconnected-(U6-Pad40)") (class "Default")
      (node (ref "U6") (pin "40") (pinfunction "40_40") (pintype "unspecified+no_connect"))
    )
    (net (code "155") (name "unconnected-(U6-Pad42)") (class "Default")
      (node (ref "U6") (pin "42") (pinfunction "42_42") (pintype "unspecified+no_connect"))
    )
    (net (code "156") (name "unconnected-(U6-Pad44)") (class "Default")
      (node (ref "U6") (pin "44") (pinfunction "44_44") (pintype "unspecified+no_connect"))
    )
    (net (code "157") (name "unconnected-(U6-Pad46)") (class "Default")
      (node (ref "U6") (pin "46") (pinfunction "46_46") (pintype "unspecified+no_connect"))
    )
    (net (code "158") (name "unconnected-(U6-Pad48)") (class "Default")
      (node (ref "U6") (pin "48") (pinfunction "48_48") (pintype "unspecified+no_connect"))
    )
    (net (code "159") (name "unconnected-(U6-Pad50)") (class "Default")
      (node (ref "U6") (pin "50") (pinfunction "50_50") (pintype "unspecified+no_connect"))
    )
    (net (code "160") (name "unconnected-(U6-Pad54)") (class "Default")
      (node (ref "U6") (pin "54") (pinfunction "54_54") (pintype "unspecified+no_connect"))
    )
    (net (code "161") (name "unconnected-(U6-Pad56)") (class "Default")
      (node (ref "U6") (pin "56") (pinfunction "56_56") (pintype "unspecified+no_connect"))
    )
    (net (code "162") (name "unconnected-(U6-Pad58)") (class "Default")
      (node (ref "U6") (pin "58") (pinfunction "58_58") (pintype "unspecified+no_connect"))
    )
    (net (code "163") (name "unconnected-(U6-Pad59)") (class "Default")
      (node (ref "U6") (pin "59") (pinfunction "59_59") (pintype "unspecified+no_connect"))
    )
    (net (code "164") (name "unconnected-(U6-Pad60)") (class "Default")
      (node (ref "U6") (pin "60") (pinfunction "60_60") (pintype "unspecified+no_connect"))
    )
    (net (code "165") (name "unconnected-(U6-Pad61)") (class "Default")
      (node (ref "U6") (pin "61") (pinfunction "61_61") (pintype "unspecified+no_connect"))
    )
    (net (code "166") (name "unconnected-(U6-Pad62)") (class "Default")
      (node (ref "U6") (pin "62") (pinfunction "62_62") (pintype "unspecified+no_connect"))
    )
    (net (code "167") (name "unconnected-(U6-Pad64)") (class "Default")
      (node (ref "U6") (pin "64") (pinfunction "64_64") (pintype "unspecified+no_connect"))
    )
    (net (code "168") (name "unconnected-(U6-Pad65)") (class "Default")
      (node (ref "U6") (pin "65") (pinfunction "65_65") (pintype "unspecified+no_connect"))
    )
    (net (code "169") (name "unconnected-(U6-Pad66)") (class "Default")
      (node (ref "U6") (pin "66") (pinfunction "66_66") (pintype "unspecified+no_connect"))
    )
    (net (code "170") (name "unconnected-(U6-Pad67)") (class "Default")
      (node (ref "U6") (pin "67") (pinfunction "67_67") (pintype "unspecified+no_connect"))
    )
    (net (code "171") (name "unconnected-(U6-Pad68)") (class "Default")
      (node (ref "U6") (pin "68") (pinfunction "68_68") (pintype "unspecified+no_connect"))
    )
    (net (code "172") (name "unconnected-(U6-Pad70)") (class "Default")
      (node (ref "U6") (pin "70") (pinfunction "70_70") (pintype "unspecified+no_connect"))
    )
    (net (code "173") (name "unconnected-(U6-Pad71)") (class "Default")
      (node (ref "U6") (pin "71") (pinfunction "71_71") (pintype "unspecified+no_connect"))
    )
    (net (code "174") (name "unconnected-(U6-Pad73)") (class "Default")
      (node (ref "U6") (pin "73") (pinfunction "73_73") (pintype "unspecified+no_connect"))
    )
    (net (code "175") (name "unconnected-(U7-Pad6)") (class "Default")
      (node (ref "U7") (pin "6") (pinfunction "6_6") (pintype "unspecified+no_connect"))
    )
    (net (code "176") (name "unconnected-(U7-Pad8)") (class "Default")
      (node (ref "U7") (pin "8") (pinfunction "8_8") (pintype "unspecified+no_connect"))
    )
    (net (code "177") (name "unconnected-(U7-Pad10)") (class "Default")
      (node (ref "U7") (pin "10") (pinfunction "10_10") (pintype "unspecified+no_connect"))
    )
    (net (code "178") (name "unconnected-(U7-Pad12)") (class "Default")
      (node (ref "U7") (pin "12") (pinfunction "12_12") (pintype "unspecified+no_connect"))
    )
    (net (code "179") (name "unconnected-(U7-Pad14)") (class "Default")
      (node (ref "U7") (pin "14") (pinfunction "14_14") (pintype "unspecified+no_connect"))
    )
    (net (code "180") (name "unconnected-(U7-Pad16)") (class "Default")
      (node (ref "U7") (pin "16") (pinfunction "16_16") (pintype "unspecified+no_connect"))
    )
    (net (code "181") (name "unconnected-(U7-Pad18)") (class "Default")
      (node (ref "U7") (pin "18") (pinfunction "18_18") (pintype "unspecified+no_connect"))
    )
    (net (code "182") (name "unconnected-(U7-Pad20)") (class "Default")
      (node (ref "U7") (pin "20") (pinfunction "20_20") (pintype "unspecified+no_connect"))
    )
    (net (code "183") (name "unconnected-(U7-Pad22)") (class "Default")
      (node (ref "U7") (pin "22") (pinfunction "22_22") (pintype "unspecified+no_connect"))
    )
    (net (code "184") (name "unconnected-(U7-Pad24)") (class "Default")
      (node (ref "U7") (pin "24") (pinfunction "24_24") (pintype "unspecified+no_connect"))
    )
    (net (code "185") (name "unconnected-(U7-Pad26)") (class "Default")
      (node (ref "U7") (pin "26") (pinfunction "26_26") (pintype "unspecified+no_connect"))
    )
    (net (code "186") (name "unconnected-(U7-Pad28)") (class "Default")
      (node (ref "U7") (pin "28") (pinfunction "28_28") (pintype "unspecified+no_connect"))
    )
    (net (code "187") (name "unconnected-(U7-Pad30)") (class "Default")
      (node (ref "U7") (pin "30") (pinfunction "30_30") (pintype "unspecified+no_connect"))
    )
    (net (code "188") (name "unconnected-(U7-Pad32)") (class "Default")
      (node (ref "U7") (pin "32") (pinfunction "32_32") (pintype "unspecified+no_connect"))
    )
    (net (code "189") (name "unconnected-(U7-Pad34)") (class "Default")
      (node (ref "U7") (pin "34") (pinfunction "34_34") (pintype "unspecified+no_connect"))
    )
    (net (code "190") (name "unconnected-(U7-Pad36)") (class "Default")
      (node (ref "U7") (pin "36") (pinfunction "36_36") (pintype "unspecified+no_connect"))
    )
    (net (code "191") (name "unconnected-(U7-Pad38)") (class "Default")
      (node (ref "U7") (pin "38") (pinfunction "38_38") (pintype "unspecified+no_connect"))
    )
    (net (code "192") (name "unconnected-(U7-Pad40)") (class "Default")
      (node (ref "U7") (pin "40") (pinfunction "40_40") (pintype "unspecified+no_connect"))
    )
    (net (code "193") (name "unconnected-(U7-Pad42)") (class "Default")
      (node (ref "U7") (pin "42") (pinfunction "42_42") (pintype "unspecified+no_connect"))
    )
    (net (code "194") (name "unconnected-(U7-Pad44)") (class "Default")
      (node (ref "U7") (pin "44") (pinfunction "44_44") (pintype "unspecified+no_connect"))
    )
    (net (code "195") (name "unconnected-(U7-Pad46)") (class "Default")
      (node (ref "U7") (pin "46") (pinfunction "46_46") (pintype "unspecified+no_connect"))
    )
    (net (code "196") (name "unconnected-(U7-Pad48)") (class "Default")
      (node (ref "U7") (pin "48") (pinfunction "48_48") (pintype "unspecified+no_connect"))
    )
    (net (code "197") (name "unconnected-(U7-Pad56)") (class "Default")
      (node (ref "U7") (pin "56") (pinfunction "56_56") (pintype "unspecified+no_connect"))
    )
    (net (code "198") (name "unconnected-(U7-Pad58)") (class "Default")
      (node (ref "U7") (pin "58") (pinfunction "58_58") (pintype "unspecified+no_connect"))
    )
    (net (code "199") (name "unconnected-(U7-Pad67)") (class "Default")
      (node (ref "U7") (pin "67") (pinfunction "67_67") (pintype "unspecified+no_connect"))
    )
    (net (code "200") (name "unconnected-(U7-Pad68)") (class "Default")
      (node (ref "U7") (pin "68") (pinfunction "68_68") (pintype "unspecified+no_connect"))
    )
    (net (code "201") (name "unconnected-(U7-Pad69)") (class "Default")
      (node (ref "U7") (pin "69") (pinfunction "69_69") (pintype "unspecified+no_connect"))
    )
    (net (code "202") (name "unconnected-(U8-CKXTAL2-Pad9)") (class "Default")
      (node (ref "U8") (pin "9") (pinfunction "CKXTAL2_9") (pintype "unspecified+no_connect"))
    )
    (net (code "203") (name "unconnected-(U8-EECS{slash}SCL-Pad31)") (class "Default")
      (node (ref "U8") (pin "31") (pinfunction "EECS/SCL_31") (pintype "unspecified+no_connect"))
    )
    (net (code "204") (name "unconnected-(U8-EEPROM_SEL{slash}PPS_PIN-Pad32)") (class "Default")
      (node (ref "U8") (pin "32") (pinfunction "EEPROM_SEL/PPS_PIN_32") (pintype "unspecified+no_connect"))
    )
    (net (code "205") (name "unconnected-(U8-GPI-Pad3)") (class "Default")
      (node (ref "U8") (pin "3") (pinfunction "GPI_3") (pintype "unspecified+no_connect"))
    )
    (net (code "206") (name "unconnected-(U8-LED3-Pad35)") (class "Default")
      (node (ref "U8") (pin "35") (pinfunction "LED3_35") (pintype "unspecified+no_connect"))
    )
    (net (code "207") (name "unconnected-(U8-NC-Pad4)") (class "Default")
      (node (ref "U8") (pin "4") (pinfunction "NC_4") (pintype "unspecified+no_connect"))
    )
    (net (code "208") (name "unconnected-(U8-NC-Pad5)") (class "Default")
      (node (ref "U8") (pin "5") (pinfunction "NC_5") (pintype "unspecified+no_connect"))
    )
    (net (code "209") (name "unconnected-(U8-NC-Pad7)") (class "Default")
      (node (ref "U8") (pin "7") (pinfunction "NC_7") (pintype "unspecified+no_connect"))
    )
    (net (code "210") (name "unconnected-(U8-SPICSB-Pad26)") (class "Default")
      (node (ref "U8") (pin "26") (pinfunction "SPICSB_26") (pintype "unspecified+no_connect"))
    )
    (net (code "211") (name "unconnected-(U9-NC{slash}PG-Pad6)") (class "Default")
      (node (ref "U9") (pin "6") (pinfunction "NC/PG_6") (pintype "unspecified+no_connect"))
    )
  )
)
